# NFT-v1_0.net
KiCad netlist of a schematic drawn in EAGLE
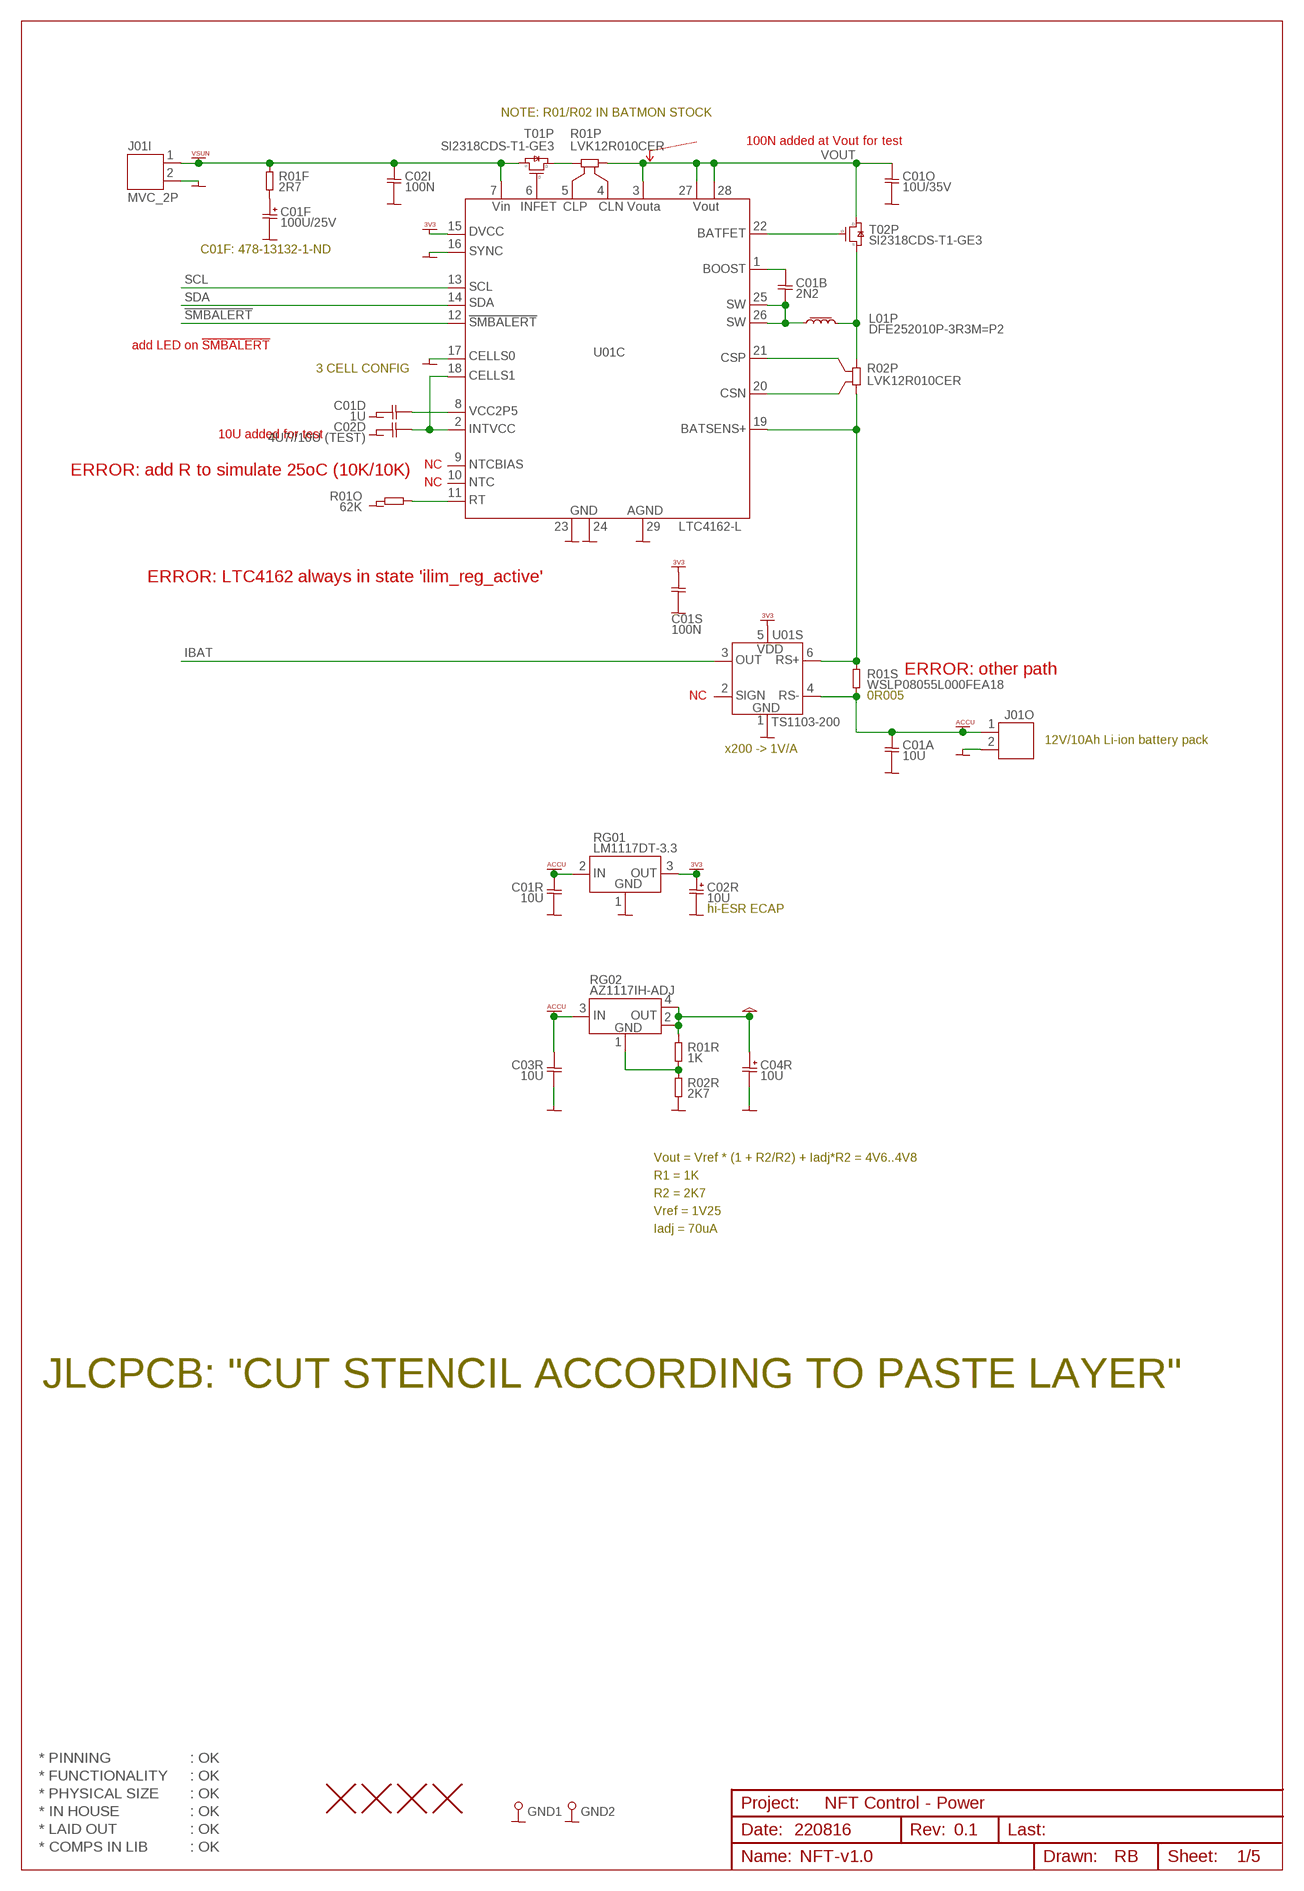
[diagram p0: schematic, sheet 1]
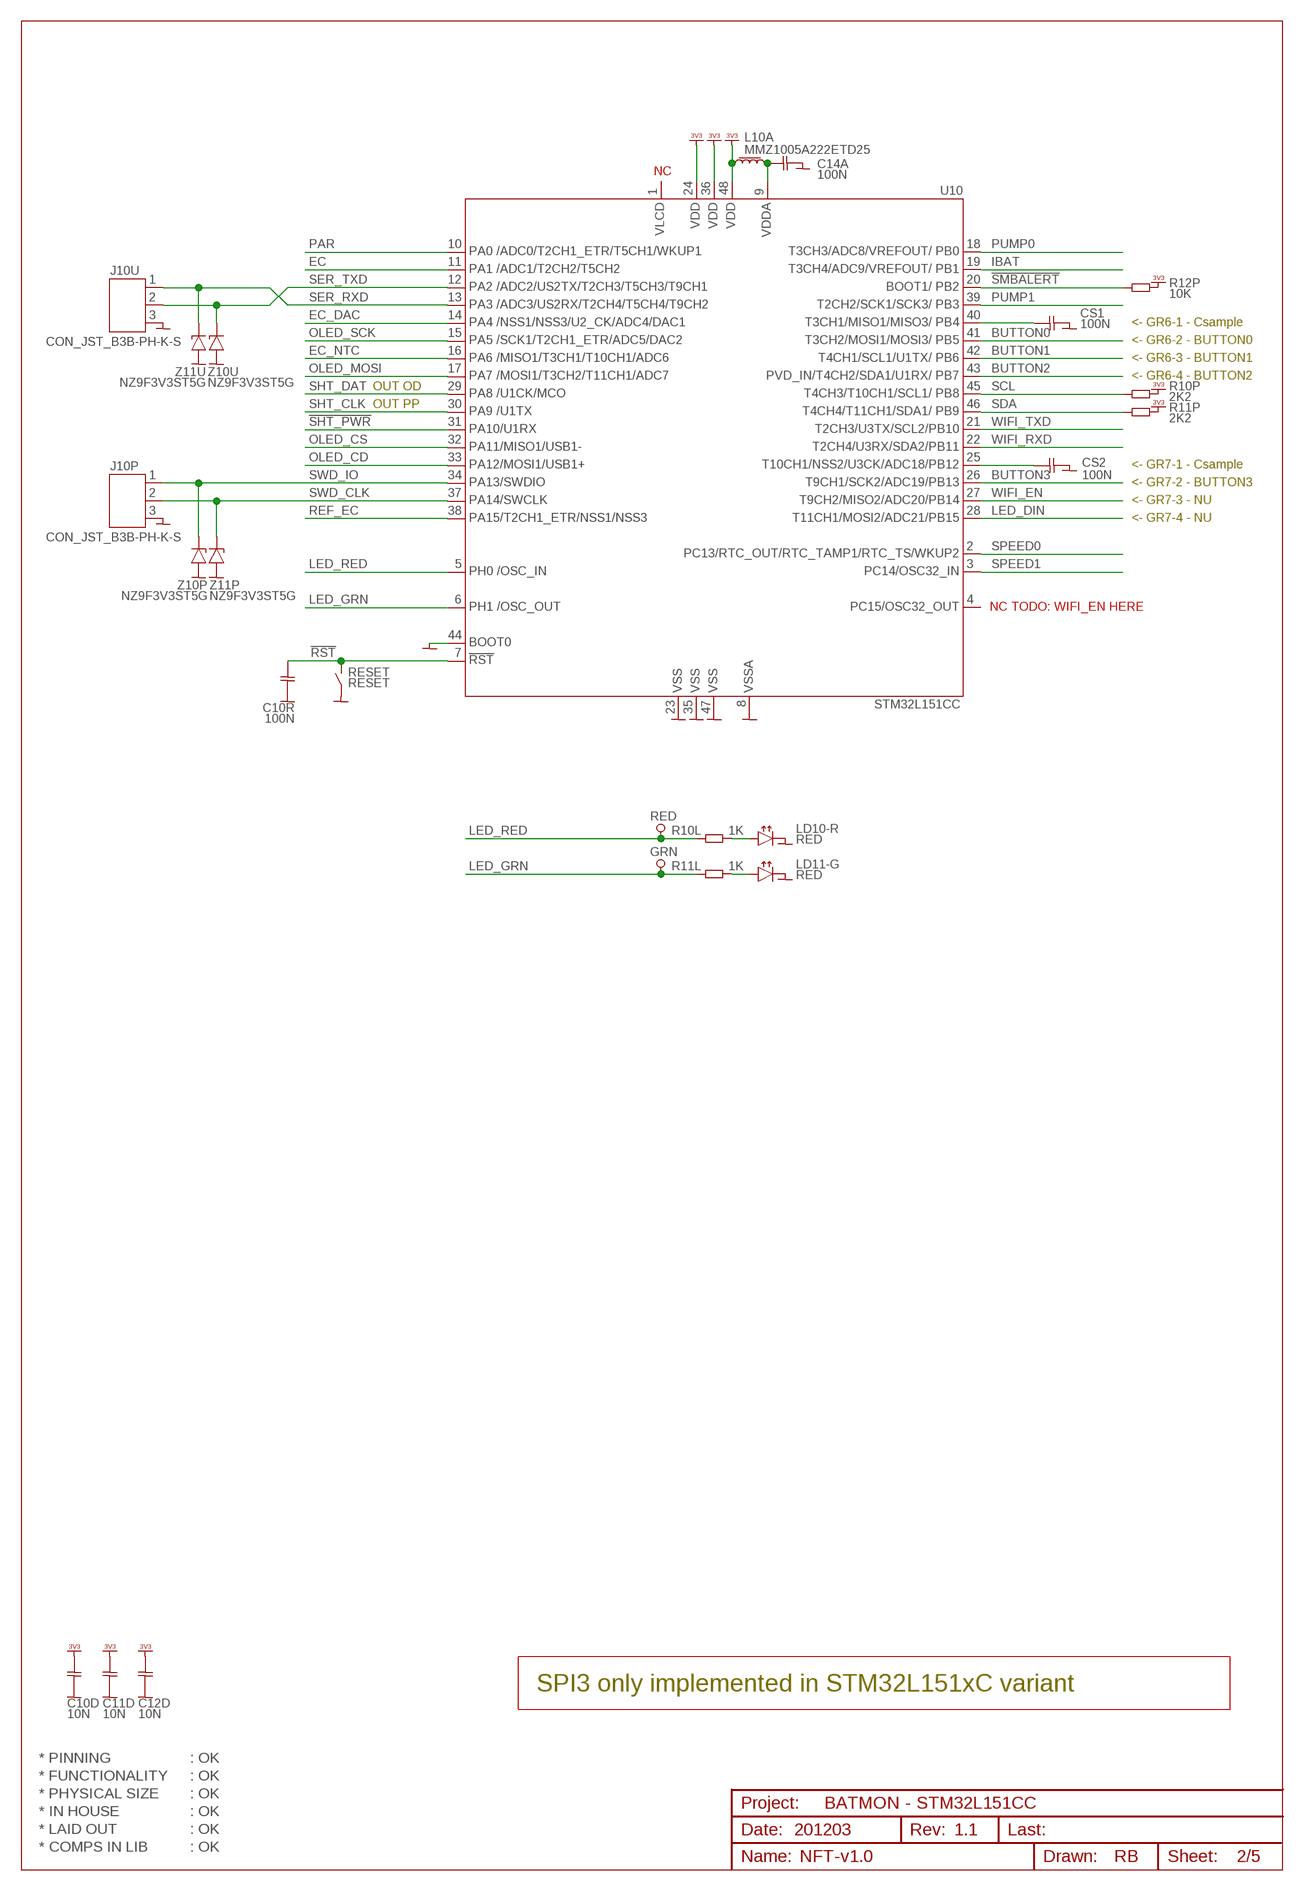
[diagram p1: schematic, sheet 2]
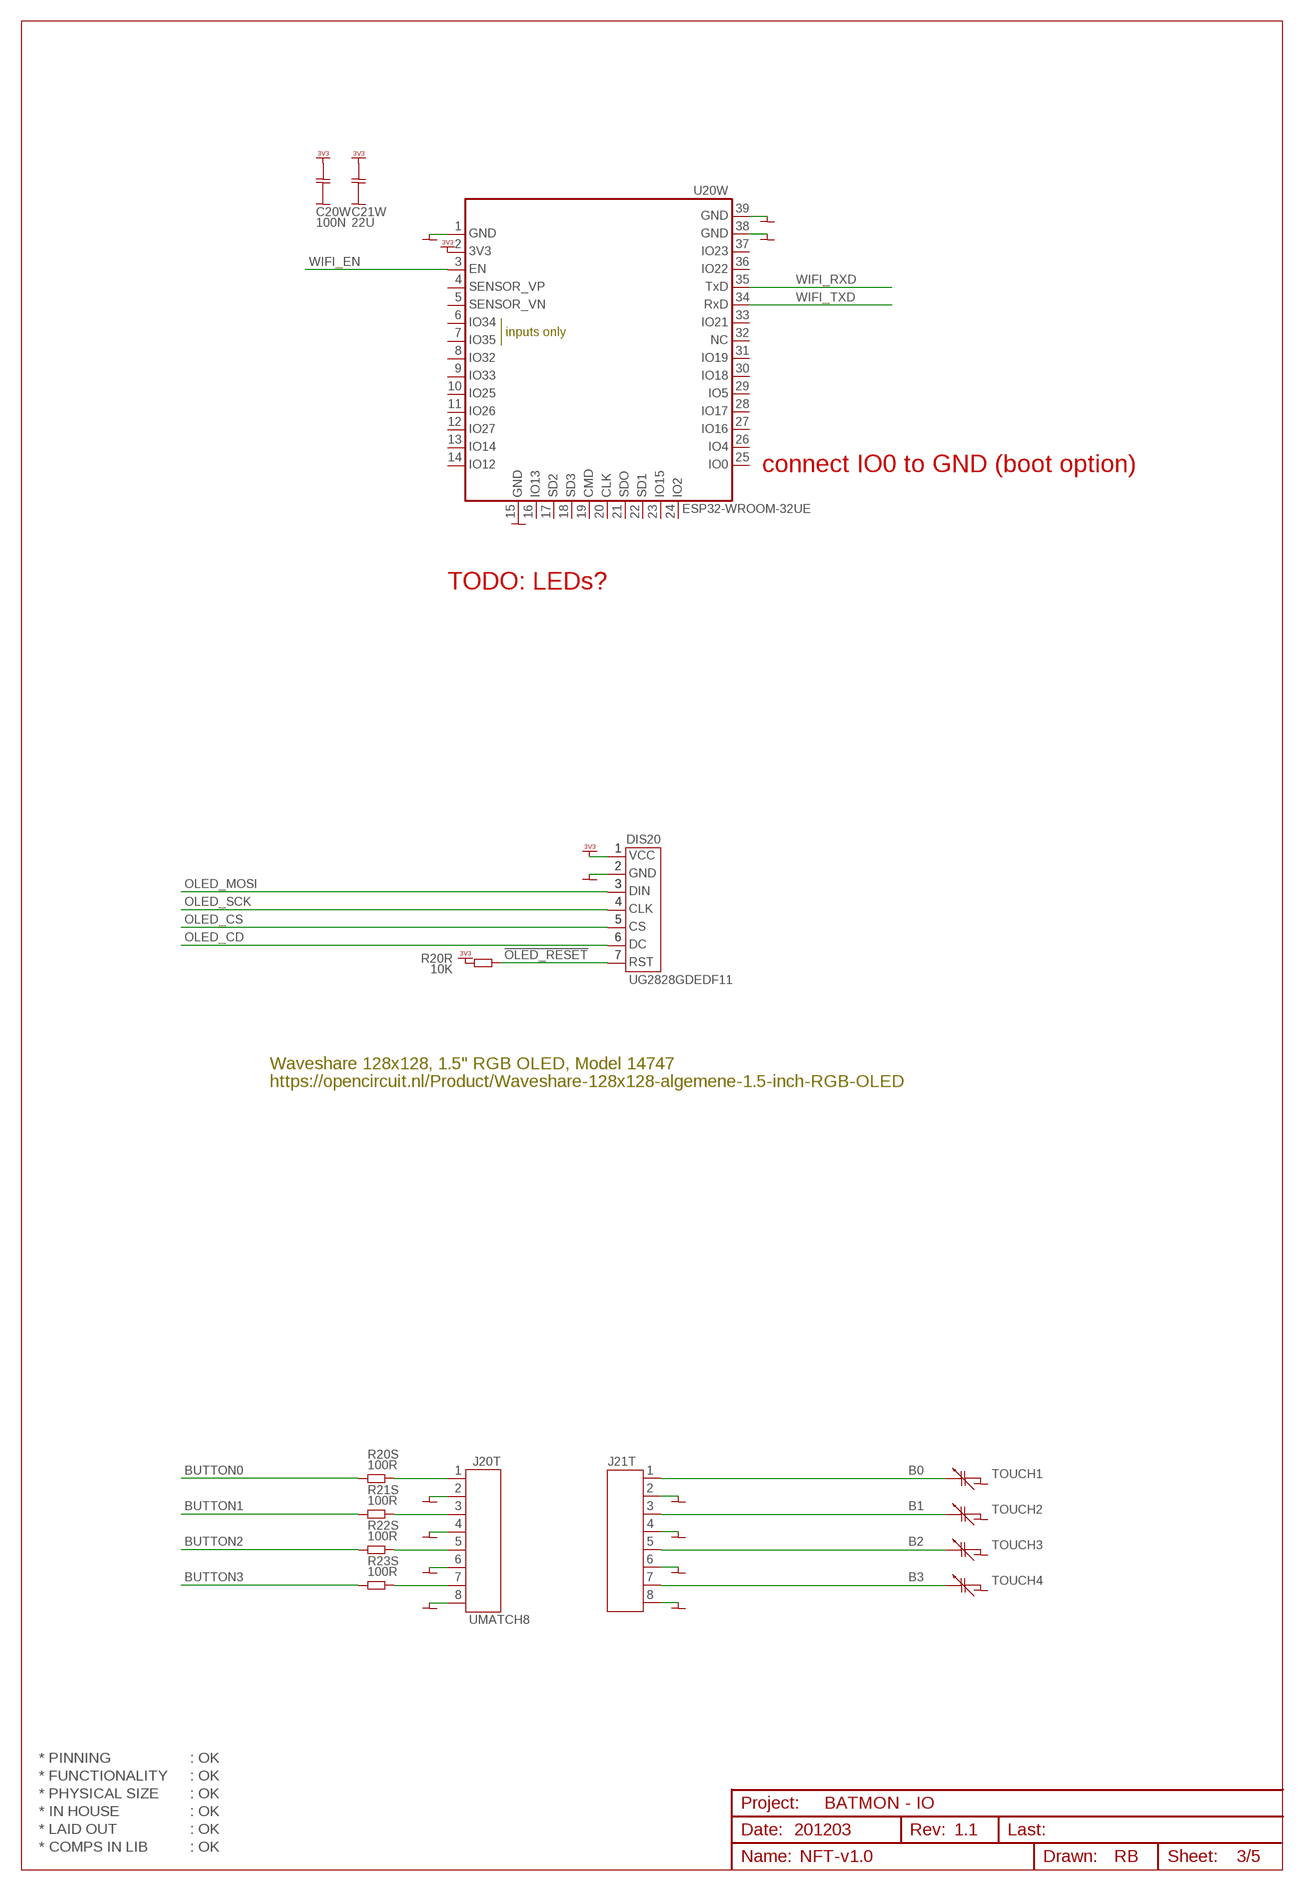
[diagram p2: schematic, sheet 3]
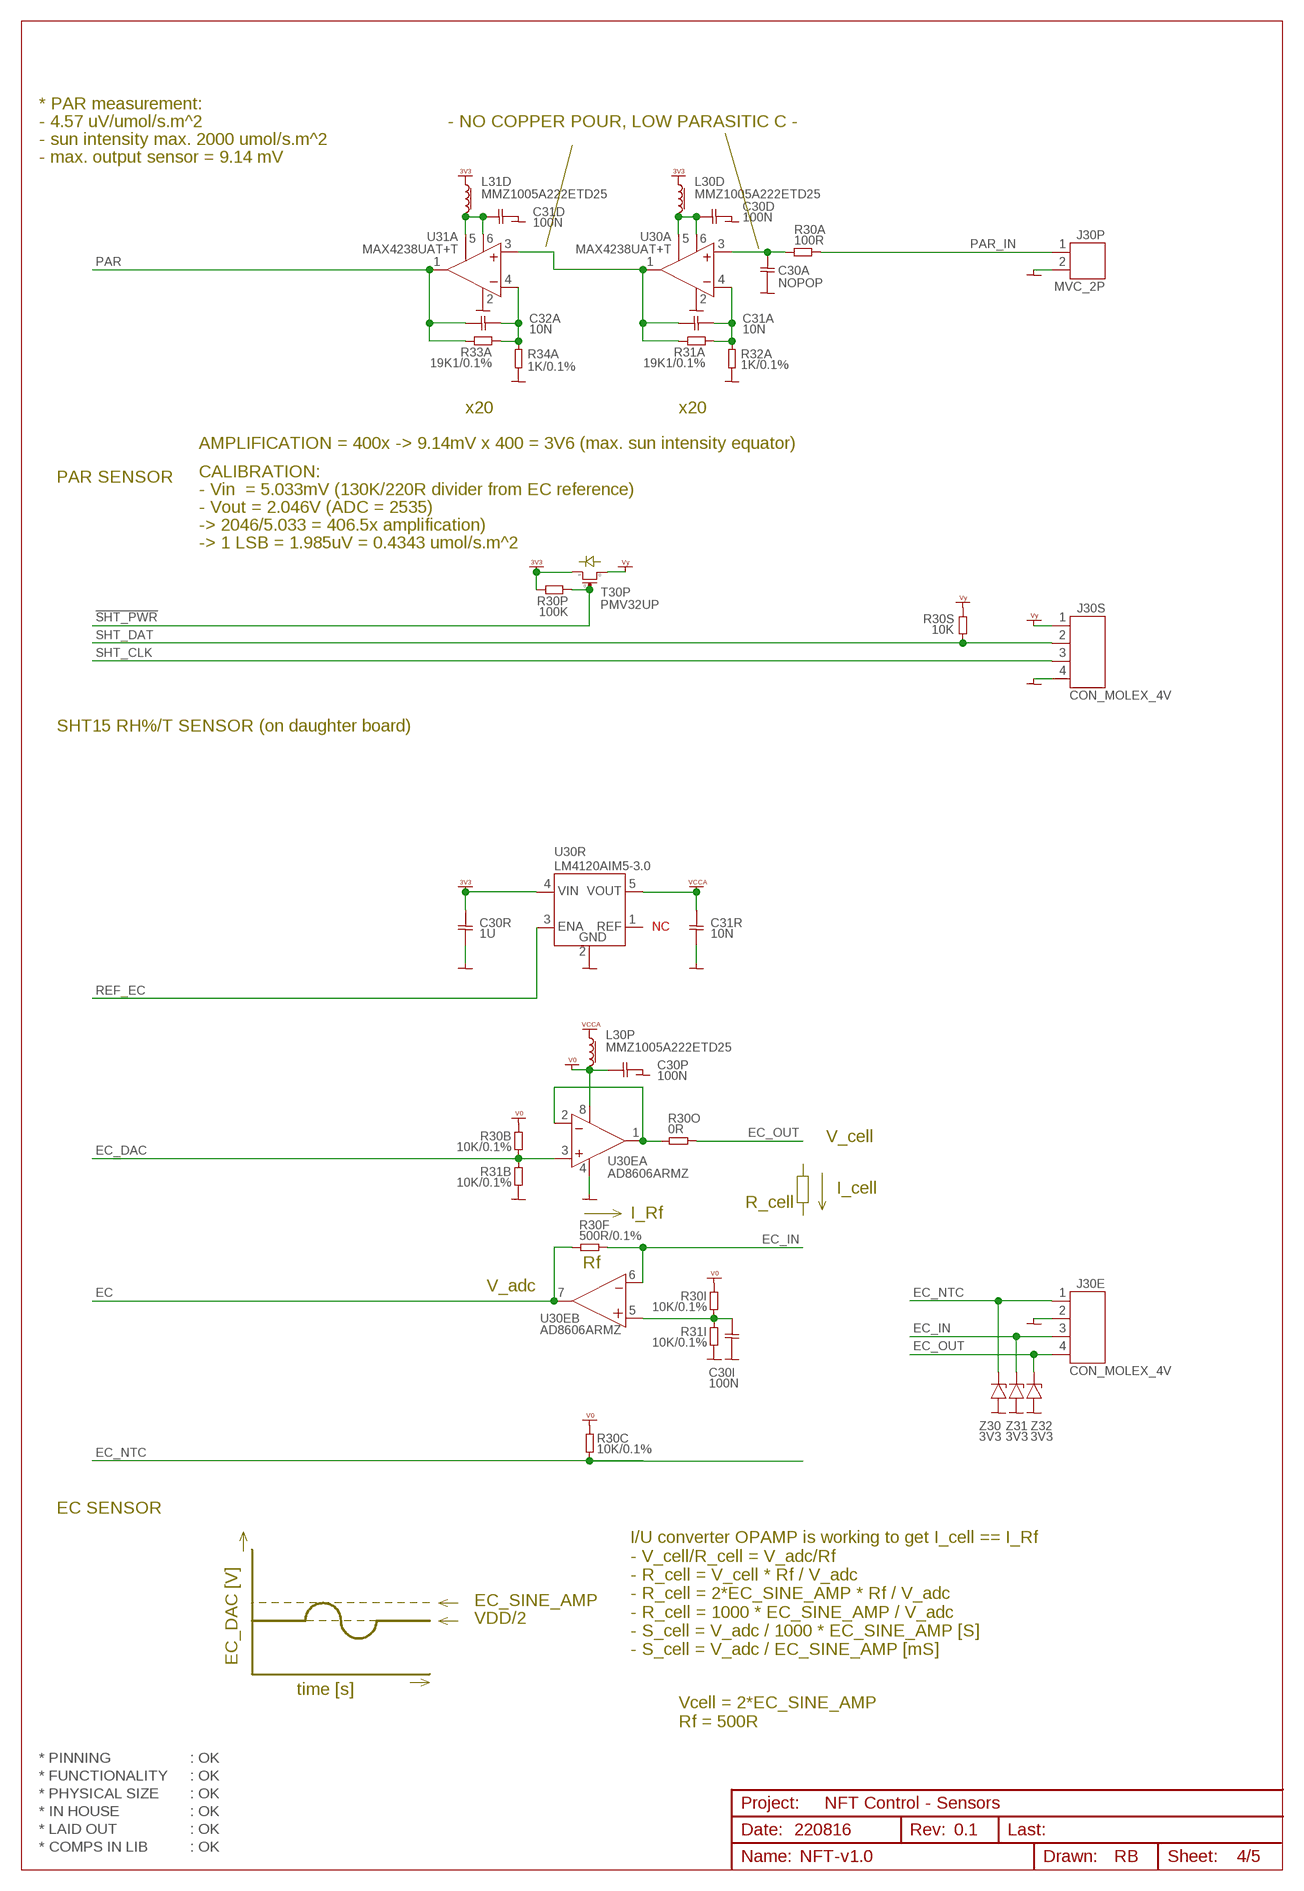
[diagram p3: schematic, sheet 4]
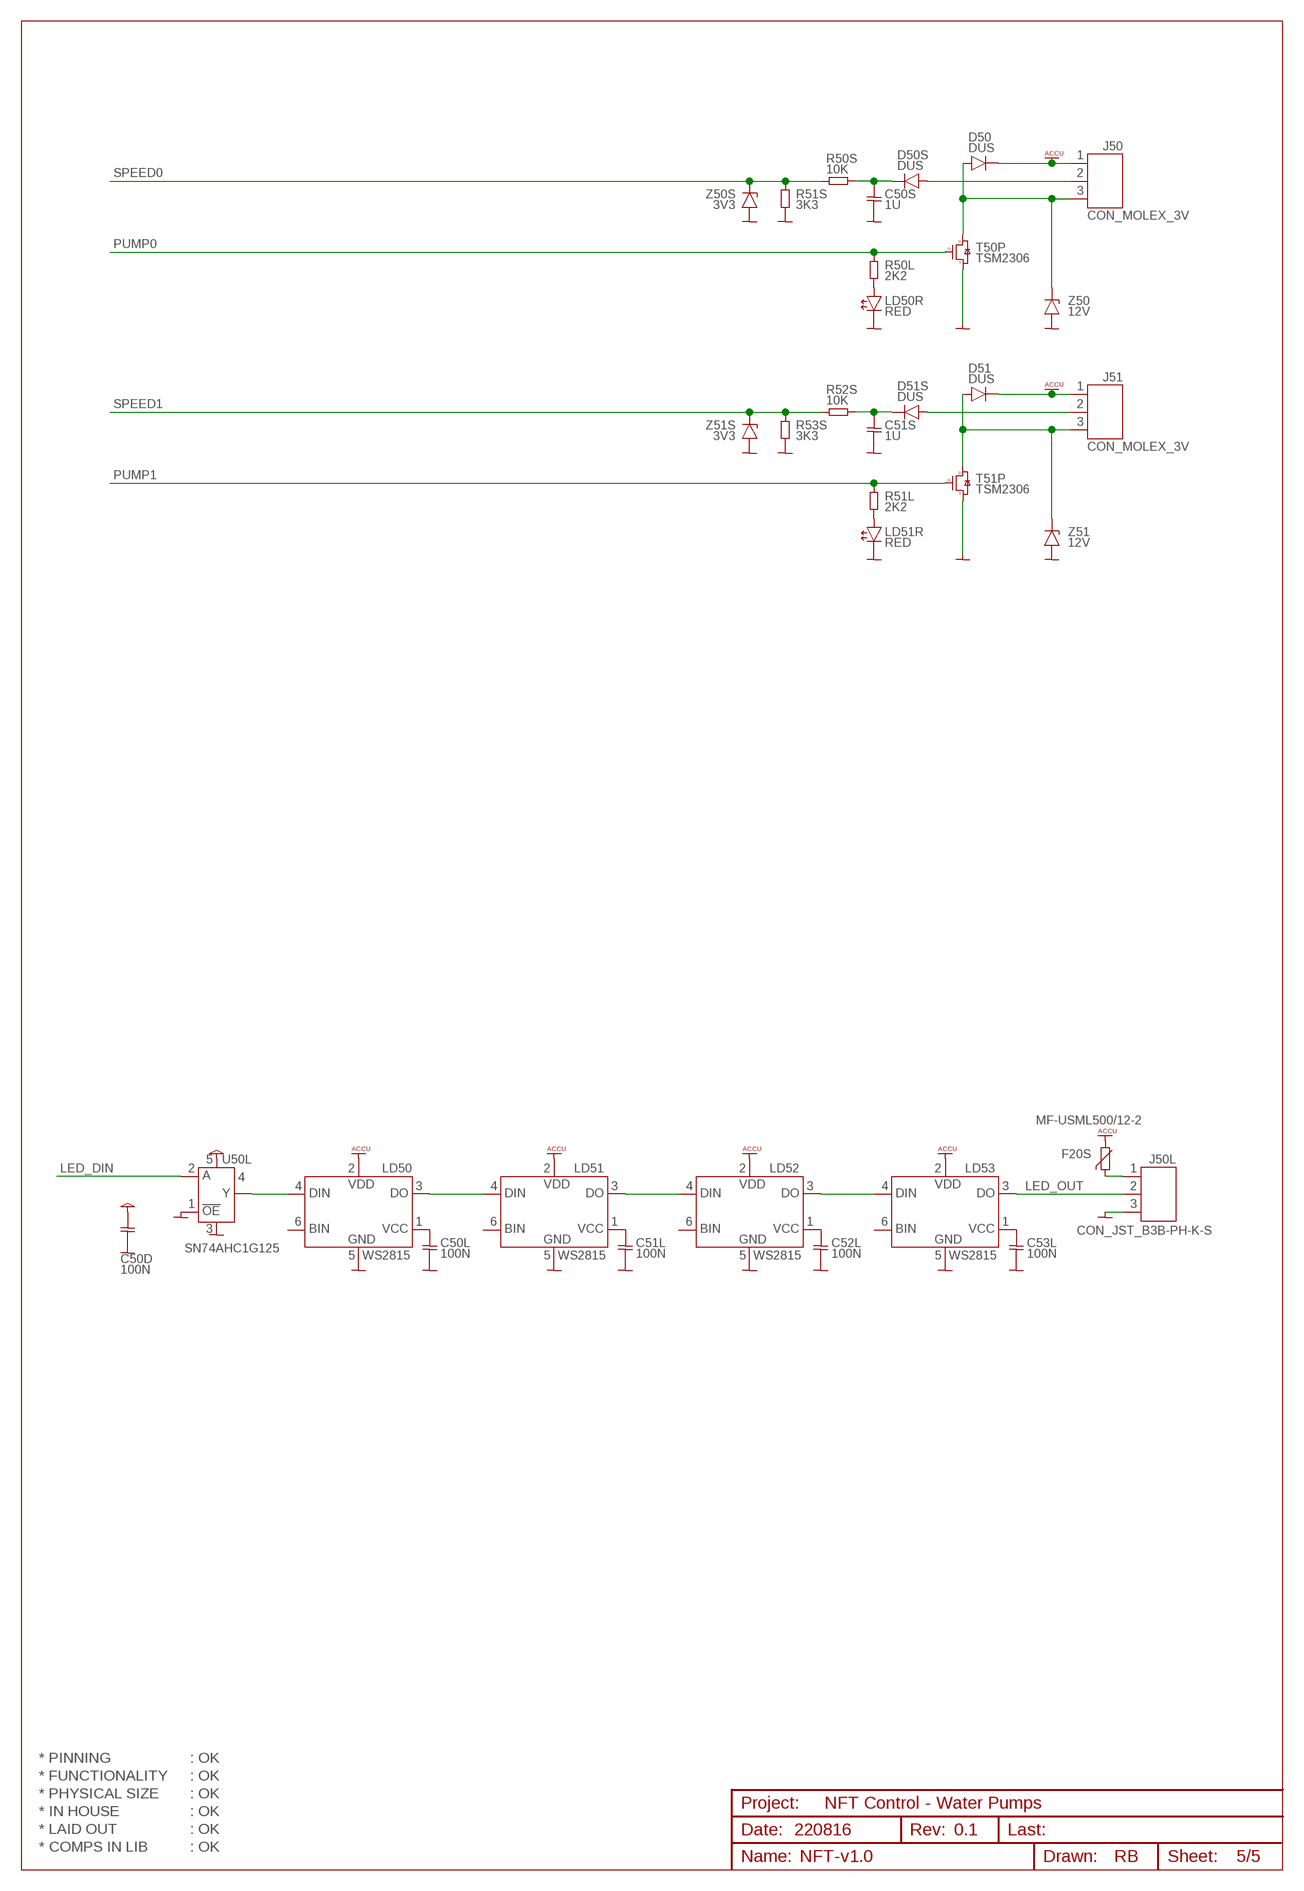
[diagram p4: schematic, sheet 5]

(export (version "E")
  (design (tool "Eeschema 10.0.6"))
  (components
    (comp (ref "C50D")
      (value "100N")
      (footprint "eagle-import:CAP0402")
      (libsource (lib "eagle-import") (part "CAP0402"))
    )
    (comp (ref "C50L")
      (value "100N")
      (footprint "eagle-import:CAP0402")
      (libsource (lib "eagle-import") (part "CAP0402"))
    )
    (comp (ref "C50S")
      (value "1U")
      (footprint "eagle-import:CAP0402")
      (libsource (lib "eagle-import") (part "CAP0402"))
    )
    (comp (ref "C51L")
      (value "100N")
      (footprint "eagle-import:CAP0402")
      (libsource (lib "eagle-import") (part "CAP0402"))
    )
    (comp (ref "C51S")
      (value "1U")
      (footprint "eagle-import:CAP0402")
      (libsource (lib "eagle-import") (part "CAP0402"))
    )
    (comp (ref "C52L")
      (value "100N")
      (footprint "eagle-import:CAP0402")
      (libsource (lib "eagle-import") (part "CAP0402"))
    )
    (comp (ref "C53L")
      (value "100N")
      (footprint "eagle-import:CAP0402")
      (libsource (lib "eagle-import") (part "CAP0402"))
    )
    (comp (ref "D50")
      (value "DUS")
      (footprint "eagle-import:DIODE_SOD323")
      (libsource (lib "eagle-import") (part "DIODE_1N4148WS"))
    )
    (comp (ref "D50S")
      (value "DUS")
      (footprint "eagle-import:DIODE_SOD323")
      (libsource (lib "eagle-import") (part "DIODE_1N4148WS"))
    )
    (comp (ref "D51")
      (value "DUS")
      (footprint "eagle-import:DIODE_SOD323")
      (libsource (lib "eagle-import") (part "DIODE_1N4148WS"))
    )
    (comp (ref "D51S")
      (value "DUS")
      (footprint "eagle-import:DIODE_SOD323")
      (libsource (lib "eagle-import") (part "DIODE_1N4148WS"))
    )
    (comp (ref "F20S")
      (value "MF-USML500/12-2")
      (footprint "eagle-import:RES1210")
      (libsource (lib "eagle-import") (part "PTC1210"))
    )
    (comp (ref "J50")
      (value "CON_MOLEX_3V")
      (footprint "eagle-import:CON_MOLEX_3V")
      (libsource (lib "eagle-import") (part "CON_MOLEX_3V"))
    )
    (comp (ref "J50L")
      (value "CON_JST_B3B-PH-K-S")
      (footprint "eagle-import:CON_JST_B3B-PH-K-S")
      (libsource (lib "eagle-import") (part "CON_JST_B3B-PH-K-S"))
    )
    (comp (ref "J51")
      (value "CON_MOLEX_3V")
      (footprint "eagle-import:CON_MOLEX_3V")
      (libsource (lib "eagle-import") (part "CON_MOLEX_3V"))
    )
    (comp (ref "LD50")
      (value "WS2815")
      (footprint "eagle-import:WS2815")
      (libsource (lib "eagle-import") (part "WS2815"))
    )
    (comp (ref "LD50R")
      (value "RED")
      (footprint "eagle-import:LED_SMD_0402")
      (libsource (lib "eagle-import") (part "LED_SMD_0402"))
    )
    (comp (ref "LD51")
      (value "WS2815")
      (footprint "eagle-import:WS2815")
      (libsource (lib "eagle-import") (part "WS2815"))
    )
    (comp (ref "LD51R")
      (value "RED")
      (footprint "eagle-import:LED_SMD_0402")
      (libsource (lib "eagle-import") (part "LED_SMD_0402"))
    )
    (comp (ref "LD52")
      (value "WS2815")
      (footprint "eagle-import:WS2815")
      (libsource (lib "eagle-import") (part "WS2815"))
    )
    (comp (ref "LD53")
      (value "WS2815")
      (footprint "eagle-import:WS2815")
      (libsource (lib "eagle-import") (part "WS2815"))
    )
    (comp (ref "R50L")
      (value "2K2")
      (footprint "eagle-import:RES0402")
      (libsource (lib "eagle-import") (part "RES0402"))
    )
    (comp (ref "R50S")
      (value "10K")
      (footprint "eagle-import:RES0402")
      (libsource (lib "eagle-import") (part "RES0402"))
    )
    (comp (ref "R51L")
      (value "2K2")
      (footprint "eagle-import:RES0402")
      (libsource (lib "eagle-import") (part "RES0402"))
    )
    (comp (ref "R51S")
      (value "3K3")
      (footprint "eagle-import:RES0402")
      (libsource (lib "eagle-import") (part "RES0402"))
    )
    (comp (ref "R52S")
      (value "10K")
      (footprint "eagle-import:RES0402")
      (libsource (lib "eagle-import") (part "RES0402"))
    )
    (comp (ref "R53S")
      (value "3K3")
      (footprint "eagle-import:RES0402")
      (libsource (lib "eagle-import") (part "RES0402"))
    )
    (comp (ref "T50P")
      (value "TSM2306")
      (footprint "eagle-import:NFET_SOT23")
      (libsource (lib "eagle-import") (part "NFET_SOT23"))
    )
    (comp (ref "T51P")
      (value "TSM2306")
      (footprint "eagle-import:NFET_SOT23")
      (libsource (lib "eagle-import") (part "NFET_SOT23"))
    )
    (comp (ref "U50L")
      (value "SN74AHC1G125")
      (footprint "eagle-import:SOT553-5")
      (libsource (lib "eagle-import") (part "SN74AHC1G125DRLR"))
    )
    (comp (ref "Z50")
      (value "12V")
      (footprint "eagle-import:ZENER_SOD80")
      (libsource (lib "eagle-import") (part "ZENER_SOD80"))
    )
    (comp (ref "Z50S")
      (value "3V3")
      (footprint "eagle-import:ZENER_SOD80")
      (libsource (lib "eagle-import") (part "ZENER_SOD80"))
    )
    (comp (ref "Z51")
      (value "12V")
      (footprint "eagle-import:ZENER_SOD80")
      (libsource (lib "eagle-import") (part "ZENER_SOD80"))
    )
    (comp (ref "Z51S")
      (value "3V3")
      (footprint "eagle-import:ZENER_SOD80")
      (libsource (lib "eagle-import") (part "ZENER_SOD80"))
    )
    (comp (ref "C10D")
      (value "10N")
      (footprint "eagle-import:CAP0402")
      (libsource (lib "eagle-import") (part "CAP0402"))
    )
    (comp (ref "C10R")
      (value "100N")
      (footprint "eagle-import:CAP0402")
      (libsource (lib "eagle-import") (part "CAP0402"))
    )
    (comp (ref "C11D")
      (value "10N")
      (footprint "eagle-import:CAP0402")
      (libsource (lib "eagle-import") (part "CAP0402"))
    )
    (comp (ref "C12D")
      (value "10N")
      (footprint "eagle-import:CAP0402")
      (libsource (lib "eagle-import") (part "CAP0402"))
    )
    (comp (ref "C14A")
      (value "100N")
      (footprint "eagle-import:CAP0402")
      (libsource (lib "eagle-import") (part "CAP0402"))
    )
    (comp (ref "CS1")
      (value "100N")
      (footprint "eagle-import:CAP0402")
      (libsource (lib "eagle-import") (part "CAP0402"))
    )
    (comp (ref "CS2")
      (value "100N")
      (footprint "eagle-import:CAP0402")
      (libsource (lib "eagle-import") (part "CAP0402"))
    )
    (comp (ref "GRN")
      (value "PIN_TEST_0.6MM")
      (footprint "eagle-import:HOLE_PTH_0.6MM")
      (libsource (lib "eagle-import") (part "PIN_TEST_0.6MM"))
    )
    (comp (ref "J10P")
      (value "CON_JST_B3B-PH-K-S")
      (footprint "eagle-import:CON_JST_B3B-PH-K-S")
      (libsource (lib "eagle-import") (part "CON_JST_B3B-PH-K-S"))
    )
    (comp (ref "J10U")
      (value "CON_JST_B3B-PH-K-S")
      (footprint "eagle-import:CON_JST_B3B-PH-K-S")
      (libsource (lib "eagle-import") (part "CON_JST_B3B-PH-K-S"))
    )
    (comp (ref "L10A")
      (value "MMZ1005A222ETD25")
      (footprint "eagle-import:L_0402")
      (libsource (lib "eagle-import") (part "L_0402_LOSSY"))
    )
    (comp (ref "LD10-R")
      (value "RED")
      (footprint "eagle-import:LED_SMD_0402")
      (libsource (lib "eagle-import") (part "LED_SMD_0402"))
    )
    (comp (ref "LD11-G")
      (value "RED")
      (footprint "eagle-import:LED_SMD_0402")
      (libsource (lib "eagle-import") (part "LED_SMD_0402"))
    )
    (comp (ref "R10L")
      (value "1K")
      (footprint "eagle-import:RES0402")
      (libsource (lib "eagle-import") (part "RES0402"))
    )
    (comp (ref "R10P")
      (value "2K2")
      (footprint "eagle-import:RES0402")
      (libsource (lib "eagle-import") (part "RES0402"))
    )
    (comp (ref "R11L")
      (value "1K")
      (footprint "eagle-import:RES0402")
      (libsource (lib "eagle-import") (part "RES0402"))
    )
    (comp (ref "R11P")
      (value "2K2")
      (footprint "eagle-import:RES0402")
      (libsource (lib "eagle-import") (part "RES0402"))
    )
    (comp (ref "R12P")
      (value "10K")
      (footprint "eagle-import:RES0402")
      (libsource (lib "eagle-import") (part "RES0402"))
    )
    (comp (ref "RED")
      (value "PIN_TEST_0.6MM")
      (footprint "eagle-import:HOLE_PTH_0.6MM")
      (libsource (lib "eagle-import") (part "PIN_TEST_0.6MM"))
    )
    (comp (ref "RESET")
      (value "RESET")
      (footprint "eagle-import:SWITCH_SMD_PBUTTON_2P")
      (libsource (lib "eagle-import") (part "SWITCH_PUSHBUTTON"))
    )
    (comp (ref "U10")
      (value "STM32L151CC")
      (footprint "eagle-import:LQFP48")
      (libsource (lib "eagle-import") (part "STM32L151CC"))
    )
    (comp (ref "Z10P")
      (value "NZ9F3V3ST5G")
      (footprint "eagle-import:ZENER_SOD923")
      (libsource (lib "eagle-import") (part "ZENER_SOD923"))
    )
    (comp (ref "Z10U")
      (value "NZ9F3V3ST5G")
      (footprint "eagle-import:ZENER_SOD923")
      (libsource (lib "eagle-import") (part "ZENER_SOD923"))
    )
    (comp (ref "Z11P")
      (value "NZ9F3V3ST5G")
      (footprint "eagle-import:ZENER_SOD923")
      (libsource (lib "eagle-import") (part "ZENER_SOD923"))
    )
    (comp (ref "Z11U")
      (value "NZ9F3V3ST5G")
      (footprint "eagle-import:ZENER_SOD923")
      (libsource (lib "eagle-import") (part "ZENER_SOD923"))
    )
    (comp (ref "C20W")
      (value "100N")
      (footprint "eagle-import:CAP0402")
      (libsource (lib "eagle-import") (part "CAP0402"))
    )
    (comp (ref "C21W")
      (value "22U")
      (footprint "eagle-import:CAP0805")
      (libsource (lib "eagle-import") (part "CAP0805"))
    )
    (comp (ref "DIS20")
      (value "UG2828GDEDF11")
      (footprint "eagle-import:WAVESHARE_1.5_OLED128X128")
      (libsource (lib "eagle-import") (part "WAVESHARE_1.5{dblquote}OLED128X128"))
    )
    (comp (ref "J20T")
      (value "UMATCH8")
      (footprint "eagle-import:CON_MICROMATCH_TOP_8F")
      (libsource (lib "eagle-import") (part "CON_MICROMATCH_8F-TOP"))
    )
    (comp (ref "J21T")
      (value "CON_MICROMATCH_8F_SMD-TOP")
      (footprint "eagle-import:CON_MICROMATCH_TOP_8F_SMD")
      (libsource (lib "eagle-import") (part "CON_MICROMATCH_8F_SMD-TOP"))
    )
    (comp (ref "R20R")
      (value "10K")
      (footprint "eagle-import:RES0402")
      (libsource (lib "eagle-import") (part "RES0402"))
    )
    (comp (ref "R20S")
      (value "100R")
      (footprint "eagle-import:RES0402")
      (libsource (lib "eagle-import") (part "RES0402"))
    )
    (comp (ref "R21S")
      (value "100R")
      (footprint "eagle-import:RES0402")
      (libsource (lib "eagle-import") (part "RES0402"))
    )
    (comp (ref "R22S")
      (value "100R")
      (footprint "eagle-import:RES0402")
      (libsource (lib "eagle-import") (part "RES0402"))
    )
    (comp (ref "R23S")
      (value "100R")
      (footprint "eagle-import:RES0402")
      (libsource (lib "eagle-import") (part "RES0402"))
    )
    (comp (ref "TOUCH1")
      (value "CAP_TOUCH_ROUND_10MM_SINGLE")
      (footprint "eagle-import:CAP_TOUCH_ROUND_10MM_SINGLE")
      (libsource (lib "eagle-import") (part "CAP_TOUCH_ROUND_10MM_SINGLE"))
    )
    (comp (ref "TOUCH2")
      (value "CAP_TOUCH_ROUND_10MM_SINGLE")
      (footprint "eagle-import:CAP_TOUCH_ROUND_10MM_SINGLE")
      (libsource (lib "eagle-import") (part "CAP_TOUCH_ROUND_10MM_SINGLE"))
    )
    (comp (ref "TOUCH3")
      (value "CAP_TOUCH_ROUND_10MM_SINGLE")
      (footprint "eagle-import:CAP_TOUCH_ROUND_10MM_SINGLE")
      (libsource (lib "eagle-import") (part "CAP_TOUCH_ROUND_10MM_SINGLE"))
    )
    (comp (ref "TOUCH4")
      (value "CAP_TOUCH_ROUND_10MM_SINGLE")
      (footprint "eagle-import:CAP_TOUCH_ROUND_10MM_SINGLE")
      (libsource (lib "eagle-import") (part "CAP_TOUCH_ROUND_10MM_SINGLE"))
    )
    (comp (ref "U20W")
      (value "ESP32-WROOM-32UE")
      (footprint "eagle-import:ESP32-WROOM-32UE")
      (libsource (lib "eagle-import") (part "ESP32-WROOM-32UE"))
    )
    (comp (ref "C01A")
      (value "10U")
      (footprint "eagle-import:CAP0805")
      (libsource (lib "eagle-import") (part "CAP0805"))
    )
    (comp (ref "C01B")
      (value "2N2")
      (footprint "eagle-import:CAP0402")
      (libsource (lib "eagle-import") (part "CAP0402"))
    )
    (comp (ref "C01D")
      (value "1U")
      (footprint "eagle-import:CAP0402")
      (libsource (lib "eagle-import") (part "CAP0402"))
    )
    (comp (ref "C01F")
      (value "100U/25V")
      (footprint "eagle-import:ECAP_SMD")
      (libsource (lib "eagle-import") (part "ECAP_SMD"))
    )
    (comp (ref "C01O")
      (value "10U/35V")
      (footprint "eagle-import:CAP0805")
      (libsource (lib "eagle-import") (part "CAP0805"))
    )
    (comp (ref "C01R")
      (value "10U")
      (footprint "eagle-import:CAP0603")
      (libsource (lib "eagle-import") (part "CAP0603"))
    )
    (comp (ref "C01S")
      (value "100N")
      (footprint "eagle-import:CAP0402")
      (libsource (lib "eagle-import") (part "CAP0402"))
    )
    (comp (ref "C02D")
      (value "4U7//10U (TEST)")
      (footprint "eagle-import:CAP0402")
      (libsource (lib "eagle-import") (part "CAP0402"))
    )
    (comp (ref "C02I")
      (value "100N")
      (footprint "eagle-import:CAP0402")
      (libsource (lib "eagle-import") (part "CAP0402"))
    )
    (comp (ref "C02R")
      (value "10U")
      (footprint "eagle-import:ECAP_SMA")
      (libsource (lib "eagle-import") (part "ECAP_SMA"))
    )
    (comp (ref "C03R")
      (value "10U")
      (footprint "eagle-import:CAP0603")
      (libsource (lib "eagle-import") (part "CAP0603"))
    )
    (comp (ref "C04R")
      (value "10U")
      (footprint "eagle-import:ECAP_SMA")
      (libsource (lib "eagle-import") (part "ECAP_SMA"))
    )
    (comp (ref "GND1")
      (value "PIN_TEST")
      (footprint "eagle-import:HOLE_PTH_0.8MM")
      (libsource (lib "eagle-import") (part "PIN_TEST"))
    )
    (comp (ref "GND2")
      (value "PIN_TEST")
      (footprint "eagle-import:HOLE_PTH_0.8MM")
      (libsource (lib "eagle-import") (part "PIN_TEST"))
    )
    (comp (ref "H1")
      (value "HOLE_NPTH_3.2MM")
      (footprint "eagle-import:HOLE_NPTH_3.2MM")
      (libsource (lib "eagle-import") (part "HOLE_NPTH_3.2MM"))
    )
    (comp (ref "H2")
      (value "HOLE_NPTH_3.2MM")
      (footprint "eagle-import:HOLE_NPTH_3.2MM")
      (libsource (lib "eagle-import") (part "HOLE_NPTH_3.2MM"))
    )
    (comp (ref "H3")
      (value "HOLE_NPTH_3.2MM")
      (footprint "eagle-import:HOLE_NPTH_3.2MM")
      (libsource (lib "eagle-import") (part "HOLE_NPTH_3.2MM"))
    )
    (comp (ref "H4")
      (value "HOLE_NPTH_3.2MM")
      (footprint "eagle-import:HOLE_NPTH_3.2MM")
      (libsource (lib "eagle-import") (part "HOLE_NPTH_3.2MM"))
    )
    (comp (ref "J01I")
      (value "MVC_2P")
      (footprint "eagle-import:CON_PHOENIX_COMBICON_MCV_HEADER_P")
      (libsource (lib "eagle-import") (part "CON_PHOENIX_COMBICON_MCV_HEADER_2P"))
    )
    (comp (ref "J01O")
      (value "CON_PHOENIX_COMBICON_MCV_HEADER_2P")
      (footprint "eagle-import:CON_PHOENIX_COMBICON_MCV_HEADER_P")
      (libsource (lib "eagle-import") (part "CON_PHOENIX_COMBICON_MCV_HEADER_2P"))
    )
    (comp (ref "L01P")
      (value "DFE252010P-3R3M=P2")
      (footprint "eagle-import:L_1008")
      (libsource (lib "eagle-import") (part "L_1008"))
    )
    (comp (ref "R01F")
      (value "2R7")
      (footprint "eagle-import:RES0603")
      (libsource (lib "eagle-import") (part "RES0603"))
    )
    (comp (ref "R01O")
      (value "62K")
      (footprint "eagle-import:RES0402")
      (libsource (lib "eagle-import") (part "RES0402"))
    )
    (comp (ref "R01P")
      (value "LVK12R010CER")
      (footprint "eagle-import:RES1206_LVK12R010CER")
      (libsource (lib "eagle-import") (part "RES1206_LVK12R010CER1206"))
    )
    (comp (ref "R01R")
      (value "1K")
      (footprint "eagle-import:RES0402")
      (libsource (lib "eagle-import") (part "RES0402"))
    )
    (comp (ref "R01S")
      (value "WSLP08055L000FEA18")
      (footprint "eagle-import:RES0805")
      (libsource (lib "eagle-import") (part "RES0805"))
    )
    (comp (ref "R02P")
      (value "LVK12R010CER")
      (footprint "eagle-import:RES1206_LVK12R010CER")
      (libsource (lib "eagle-import") (part "RES1206_LVK12R010CER1206"))
    )
    (comp (ref "R02R")
      (value "2K7")
      (footprint "eagle-import:RES0402")
      (libsource (lib "eagle-import") (part "RES0402"))
    )
    (comp (ref "RG01")
      (value "LM1117DT-3.3")
      (footprint "eagle-import:TO252")
      (libsource (lib "eagle-import") (part "LM1117DT-3.3"))
    )
    (comp (ref "RG02")
      (value "AZ1117IH-ADJ")
      (footprint "eagle-import:SOT223")
      (libsource (lib "eagle-import") (part "AZ1117IH-ADJ"))
    )
    (comp (ref "T01P")
      (value "SI2318CDS-T1-GE3")
      (footprint "eagle-import:NFET_SOT23")
      (libsource (lib "eagle-import") (part "NFET_SOT23"))
    )
    (comp (ref "T02P")
      (value "SI2318CDS-T1-GE3")
      (footprint "eagle-import:NFET_SOT23")
      (libsource (lib "eagle-import") (part "NFET_SOT23"))
    )
    (comp (ref "U01C")
      (value "LTC4162-L")
      (footprint "eagle-import:QFN28_4X5")
      (libsource (lib "eagle-import") (part "LTC4162-L"))
    )
    (comp (ref "U01S")
      (value "TS1103-200")
      (footprint "eagle-import:SOT23-6")
      (libsource (lib "eagle-import") (part "TS1103-200"))
    )
    (comp (ref "C30A")
      (value "NOPOP")
      (footprint "eagle-import:CAP0402")
      (libsource (lib "eagle-import") (part "CAP0402"))
    )
    (comp (ref "C30D")
      (value "100N")
      (footprint "eagle-import:CAP0402")
      (libsource (lib "eagle-import") (part "CAP0402"))
    )
    (comp (ref "C30I")
      (value "100N")
      (footprint "eagle-import:CAP0402")
      (libsource (lib "eagle-import") (part "CAP0402"))
    )
    (comp (ref "C30P")
      (value "100N")
      (footprint "eagle-import:CAP0402")
      (libsource (lib "eagle-import") (part "CAP0402"))
    )
    (comp (ref "C30R")
      (value "1U")
      (footprint "eagle-import:CAP0402")
      (libsource (lib "eagle-import") (part "CAP0402"))
    )
    (comp (ref "C31A")
      (value "10N")
      (footprint "eagle-import:CAP0402")
      (libsource (lib "eagle-import") (part "CAP0402"))
    )
    (comp (ref "C31D")
      (value "100N")
      (footprint "eagle-import:CAP0402")
      (libsource (lib "eagle-import") (part "CAP0402"))
    )
    (comp (ref "C31R")
      (value "10N")
      (footprint "eagle-import:CAP0402")
      (libsource (lib "eagle-import") (part "CAP0402"))
    )
    (comp (ref "C32A")
      (value "10N")
      (footprint "eagle-import:CAP0402")
      (libsource (lib "eagle-import") (part "CAP0402"))
    )
    (comp (ref "J30E")
      (value "CON_MOLEX_4V")
      (footprint "eagle-import:CON_MOLEX_4V")
      (libsource (lib "eagle-import") (part "CON_MOLEX_4V"))
    )
    (comp (ref "J30P")
      (value "MVC_2P")
      (footprint "eagle-import:CON_PHOENIX_COMBICON_MCV_HEADER_P")
      (libsource (lib "eagle-import") (part "CON_PHOENIX_COMBICON_MCV_HEADER_2P"))
    )
    (comp (ref "J30S")
      (value "CON_MOLEX_4V")
      (footprint "eagle-import:CON_MOLEX_4V")
      (libsource (lib "eagle-import") (part "CON_MOLEX_4V"))
    )
    (comp (ref "L30D")
      (value "MMZ1005A222ETD25")
      (footprint "eagle-import:L_0402")
      (libsource (lib "eagle-import") (part "L_0402_LOSSY"))
    )
    (comp (ref "L30P")
      (value "MMZ1005A222ETD25")
      (footprint "eagle-import:L_0402")
      (libsource (lib "eagle-import") (part "L_0402_LOSSY"))
    )
    (comp (ref "L31D")
      (value "MMZ1005A222ETD25")
      (footprint "eagle-import:L_0402")
      (libsource (lib "eagle-import") (part "L_0402_LOSSY"))
    )
    (comp (ref "R30A")
      (value "100R")
      (footprint "eagle-import:RES0402")
      (libsource (lib "eagle-import") (part "RES0402"))
    )
    (comp (ref "R30B")
      (value "10K/0.1%")
      (footprint "eagle-import:RES0402")
      (libsource (lib "eagle-import") (part "RES0402"))
    )
    (comp (ref "R30C")
      (value "10K/0.1%")
      (footprint "eagle-import:RES0402")
      (libsource (lib "eagle-import") (part "RES0402"))
    )
    (comp (ref "R30F")
      (value "500R/0.1%")
      (footprint "eagle-import:RES0402")
      (libsource (lib "eagle-import") (part "RES0402"))
    )
    (comp (ref "R30I")
      (value "10K/0.1%")
      (footprint "eagle-import:RES0402")
      (libsource (lib "eagle-import") (part "RES0402"))
    )
    (comp (ref "R30O")
      (value "0R")
      (footprint "eagle-import:RES0402")
      (libsource (lib "eagle-import") (part "RES0402"))
    )
    (comp (ref "R30P")
      (value "100K")
      (footprint "eagle-import:RES0402")
      (libsource (lib "eagle-import") (part "RES0402"))
    )
    (comp (ref "R30S")
      (value "10K")
      (footprint "eagle-import:RES0402")
      (libsource (lib "eagle-import") (part "RES0402"))
    )
    (comp (ref "R31A")
      (value "19K1/0.1%")
      (footprint "eagle-import:RES0402")
      (libsource (lib "eagle-import") (part "RES0402"))
    )
    (comp (ref "R31B")
      (value "10K/0.1%")
      (footprint "eagle-import:RES0402")
      (libsource (lib "eagle-import") (part "RES0402"))
    )
    (comp (ref "R31I")
      (value "10K/0.1%")
      (footprint "eagle-import:RES0402")
      (libsource (lib "eagle-import") (part "RES0402"))
    )
    (comp (ref "R32A")
      (value "1K/0.1%")
      (footprint "eagle-import:RES0402")
      (libsource (lib "eagle-import") (part "RES0402"))
    )
    (comp (ref "R33A")
      (value "19K1/0.1%")
      (footprint "eagle-import:RES0402")
      (libsource (lib "eagle-import") (part "RES0402"))
    )
    (comp (ref "R34A")
      (value "1K/0.1%")
      (footprint "eagle-import:RES0402")
      (libsource (lib "eagle-import") (part "RES0402"))
    )
    (comp (ref "T30P")
      (value "PMV32UP")
      (footprint "eagle-import:PFET_SOT23")
      (libsource (lib "eagle-import") (part "PFET_SOT23"))
    )
    (comp (ref "U30A")
      (value "MAX4238UAT+T")
      (footprint "eagle-import:SOT23-6")
      (libsource (lib "eagle-import") (part "MAX4238UAT+T"))
    )
    (comp (ref "U30E")
      (value "AD8606ARMZ")
      (footprint "eagle-import:MSOP8")
      (libsource (lib "eagle-import") (part "AD8606ARMZ"))
    )
    (comp (ref "U30R")
      (value "LM4120AIM5-3.0")
      (footprint "eagle-import:SOT23-5")
      (libsource (lib "eagle-import") (part "LM4120AIM5-3.0"))
    )
    (comp (ref "U31A")
      (value "MAX4238UAT+T")
      (footprint "eagle-import:SOT23-6")
      (libsource (lib "eagle-import") (part "MAX4238UAT+T"))
    )
    (comp (ref "Z30")
      (value "3V3")
      (footprint "eagle-import:ZENER_SOD80")
      (libsource (lib "eagle-import") (part "ZENER_SOD80"))
    )
    (comp (ref "Z31")
      (value "3V3")
      (footprint "eagle-import:ZENER_SOD80")
      (libsource (lib "eagle-import") (part "ZENER_SOD80"))
    )
    (comp (ref "Z32")
      (value "3V3")
      (footprint "eagle-import:ZENER_SOD80")
      (libsource (lib "eagle-import") (part "ZENER_SOD80"))
    )
  )
  (nets
    (net (code "1") (name "ACCU") (class "Default")
      (node (ref "C01A") (pin "1") (pinfunction "1_1") (pintype "passive"))
      (node (ref "C01R") (pin "1") (pinfunction "1_1") (pintype "passive"))
      (node (ref "C03R") (pin "1") (pinfunction "1_1") (pintype "passive"))
      (node (ref "D50") (pin "1-") (pinfunction "-_1-") (pintype "passive"))
      (node (ref "D51") (pin "1-") (pinfunction "-_1-") (pintype "passive"))
      (node (ref "F20S") (pin "2") (pinfunction "P$2_2") (pintype "passive"))
      (node (ref "J01O") (pin "1") (pinfunction "1_1") (pintype "passive"))
      (node (ref "J50") (pin "1") (pinfunction "1_1") (pintype "passive"))
      (node (ref "J51") (pin "1") (pinfunction "1_1") (pintype "passive"))
      (node (ref "LD50") (pin "2") (pinfunction "2.VDD_2") (pintype "passive"))
      (node (ref "LD51") (pin "2") (pinfunction "2.VDD_2") (pintype "passive"))
      (node (ref "LD52") (pin "2") (pinfunction "2.VDD_2") (pintype "passive"))
      (node (ref "LD53") (pin "2") (pinfunction "2.VDD_2") (pintype "passive"))
      (node (ref "R01S") (pin "2") (pinfunction "2_2") (pintype "passive"))
      (node (ref "RG01") (pin "2") (pinfunction "2.IN_2") (pintype "passive"))
      (node (ref "RG02") (pin "3") (pinfunction "3.IN_3") (pintype "passive"))
      (node (ref "U01S") (pin "4") (pinfunction "4.RS-_4") (pintype "passive"))
    )
    (net (code "2") (name "B0") (class "Default")
      (node (ref "J20T") (pin "1") (pinfunction "1_1") (pintype "passive"))
      (node (ref "J21T") (pin "1") (pinfunction "1_1") (pintype "passive"))
      (node (ref "R20S") (pin "2") (pinfunction "2_2") (pintype "passive"))
      (node (ref "TOUCH1") (pin "1") (pinfunction "1_1") (pintype "passive"))
    )
    (net (code "3") (name "B1") (class "Default")
      (node (ref "J20T") (pin "3") (pinfunction "3_3") (pintype "passive"))
      (node (ref "J21T") (pin "3") (pinfunction "3_3") (pintype "passive"))
      (node (ref "R21S") (pin "2") (pinfunction "2_2") (pintype "passive"))
      (node (ref "TOUCH2") (pin "1") (pinfunction "1_1") (pintype "passive"))
    )
    (net (code "4") (name "B2") (class "Default")
      (node (ref "J20T") (pin "5") (pinfunction "5_5") (pintype "passive"))
      (node (ref "J21T") (pin "5") (pinfunction "5_5") (pintype "passive"))
      (node (ref "R22S") (pin "2") (pinfunction "2_2") (pintype "passive"))
      (node (ref "TOUCH3") (pin "1") (pinfunction "1_1") (pintype "passive"))
    )
    (net (code "5") (name "B3") (class "Default")
      (node (ref "J20T") (pin "7") (pinfunction "7_7") (pintype "passive"))
      (node (ref "J21T") (pin "7") (pinfunction "7_7") (pintype "passive"))
      (node (ref "R23S") (pin "2") (pinfunction "2_2") (pintype "passive"))
      (node (ref "TOUCH4") (pin "1") (pinfunction "1_1") (pintype "passive"))
    )
    (net (code "6") (name "BUTTON0") (class "Default")
      (node (ref "R20S") (pin "1") (pinfunction "1_1") (pintype "passive"))
      (node (ref "U10") (pin "41") (pinfunction "41.PB5_41") (pintype "passive"))
    )
    (net (code "7") (name "BUTTON1") (class "Default")
      (node (ref "R21S") (pin "1") (pinfunction "1_1") (pintype "passive"))
      (node (ref "U10") (pin "42") (pinfunction "42.PB6_42") (pintype "passive"))
    )
    (net (code "8") (name "BUTTON2") (class "Default")
      (node (ref "R22S") (pin "1") (pinfunction "1_1") (pintype "passive"))
      (node (ref "U10") (pin "43") (pinfunction "43.PB7_43") (pintype "passive"))
    )
    (net (code "9") (name "BUTTON3") (class "Default")
      (node (ref "R23S") (pin "1") (pinfunction "1_1") (pintype "passive"))
      (node (ref "U10") (pin "26") (pinfunction "26.PB13_26") (pintype "passive"))
    )
    (net (code "10") (name "EC") (class "Default")
      (node (ref "R30F") (pin "2") (pinfunction "2_2") (pintype "passive"))
      (node (ref "U10") (pin "11") (pinfunction "11.PA1_11") (pintype "passive"))
      (node (ref "U30E") (pin "7") (pinfunction "7.OUT_7") (pintype "passive"))
    )
    (net (code "11") (name "EC_DAC") (class "Default")
      (node (ref "R30B") (pin "2") (pinfunction "2_2") (pintype "passive"))
      (node (ref "R31B") (pin "1") (pinfunction "1_1") (pintype "passive"))
      (node (ref "U10") (pin "14") (pinfunction "14.PA4_14") (pintype "passive"))
      (node (ref "U30E") (pin "3") (pinfunction "3.IN+_3") (pintype "passive"))
    )
    (net (code "12") (name "EC_IN") (class "Default")
      (node (ref "J30E") (pin "3") (pinfunction "3_3") (pintype "passive"))
      (node (ref "R30F") (pin "1") (pinfunction "1_1") (pintype "passive"))
      (node (ref "U30E") (pin "6") (pinfunction "6.IN-_6") (pintype "passive"))
      (node (ref "Z31") (pin "2") (pinfunction "C_2") (pintype "passive"))
    )
    (net (code "13") (name "EC_NTC") (class "Default")
      (node (ref "J30E") (pin "1") (pinfunction "1_1") (pintype "passive"))
      (node (ref "R30C") (pin "2") (pinfunction "2_2") (pintype "passive"))
      (node (ref "U10") (pin "16") (pinfunction "16.PA6_16") (pintype "passive"))
      (node (ref "Z30") (pin "2") (pinfunction "C_2") (pintype "passive"))
    )
    (net (code "14") (name "EC_OUT") (class "Default")
      (node (ref "J30E") (pin "4") (pinfunction "4_4") (pintype "passive"))
      (node (ref "R30O") (pin "1") (pinfunction "1_1") (pintype "passive"))
      (node (ref "Z32") (pin "2") (pinfunction "C_2") (pintype "passive"))
    )
    (net (code "15") (name "GND") (class "Default")
      (node (ref "C01A") (pin "2") (pinfunction "2_2") (pintype "passive"))
      (node (ref "C01D") (pin "1") (pinfunction "1_1") (pintype "passive"))
      (node (ref "C01F") (pin "-") (pinfunction "-_-") (pintype "passive"))
      (node (ref "C01O") (pin "2") (pinfunction "2_2") (pintype "passive"))
      (node (ref "C01R") (pin "2") (pinfunction "2_2") (pintype "passive"))
      (node (ref "C01S") (pin "2") (pinfunction "2_2") (pintype "passive"))
      (node (ref "C02D") (pin "1") (pinfunction "1_1") (pintype "passive"))
      (node (ref "C02I") (pin "2") (pinfunction "2_2") (pintype "passive"))
      (node (ref "C02R") (pin "-") (pinfunction "-_-") (pintype "passive"))
      (node (ref "C03R") (pin "2") (pinfunction "2_2") (pintype "passive"))
      (node (ref "C04R") (pin "-") (pinfunction "-_-") (pintype "passive"))
      (node (ref "C10D") (pin "2") (pinfunction "2_2") (pintype "passive"))
      (node (ref "C10R") (pin "2") (pinfunction "2_2") (pintype "passive"))
      (node (ref "C11D") (pin "2") (pinfunction "2_2") (pintype "passive"))
      (node (ref "C12D") (pin "2") (pinfunction "2_2") (pintype "passive"))
      (node (ref "C14A") (pin "2") (pinfunction "2_2") (pintype "passive"))
      (node (ref "C20W") (pin "2") (pinfunction "2_2") (pintype "passive"))
      (node (ref "C21W") (pin "2") (pinfunction "2_2") (pintype "passive"))
      (node (ref "C30A") (pin "1") (pinfunction "1_1") (pintype "passive"))
      (node (ref "C30D") (pin "2") (pinfunction "2_2") (pintype "passive"))
      (node (ref "C30I") (pin "1") (pinfunction "1_1") (pintype "passive"))
      (node (ref "C30P") (pin "2") (pinfunction "2_2") (pintype "passive"))
      (node (ref "C30R") (pin "2") (pinfunction "2_2") (pintype "passive"))
      (node (ref "C31D") (pin "2") (pinfunction "2_2") (pintype "passive"))
      (node (ref "C31R") (pin "2") (pinfunction "2_2") (pintype "passive"))
      (node (ref "C50D") (pin "2") (pinfunction "2_2") (pintype "passive"))
      (node (ref "C50L") (pin "2") (pinfunction "2_2") (pintype "passive"))
      (node (ref "C50S") (pin "2") (pinfunction "2_2") (pintype "passive"))
      (node (ref "C51L") (pin "2") (pinfunction "2_2") (pintype "passive"))
      (node (ref "C51S") (pin "2") (pinfunction "2_2") (pintype "passive"))
      (node (ref "C52L") (pin "2") (pinfunction "2_2") (pintype "passive"))
      (node (ref "C53L") (pin "2") (pinfunction "2_2") (pintype "passive"))
      (node (ref "CS1") (pin "2") (pinfunction "2_2") (pintype "passive"))
      (node (ref "CS2") (pin "2") (pinfunction "2_2") (pintype "passive"))
      (node (ref "DIS20") (pin "2") (pinfunction "2.GND_2") (pintype "passive"))
      (node (ref "GND1") (pin "1") (pinfunction "P$1_1") (pintype "passive"))
      (node (ref "GND2") (pin "1") (pinfunction "P$1_1") (pintype "passive"))
      (node (ref "J01I") (pin "2") (pinfunction "2_2") (pintype "passive"))
      (node (ref "J01O") (pin "2") (pinfunction "2_2") (pintype "passive"))
      (node (ref "J10P") (pin "3") (pinfunction "3_3") (pintype "passive"))
      (node (ref "J10U") (pin "3") (pinfunction "3_3") (pintype "passive"))
      (node (ref "J20T") (pin "2") (pinfunction "2_2") (pintype "passive"))
      (node (ref "J20T") (pin "4") (pinfunction "4_4") (pintype "passive"))
      (node (ref "J20T") (pin "6") (pinfunction "6_6") (pintype "passive"))
      (node (ref "J20T") (pin "8") (pinfunction "8_8") (pintype "passive"))
      (node (ref "J21T") (pin "2") (pinfunction "2_2") (pintype "passive"))
      (node (ref "J21T") (pin "4") (pinfunction "4_4") (pintype "passive"))
      (node (ref "J21T") (pin "6") (pinfunction "6_6") (pintype "passive"))
      (node (ref "J21T") (pin "8") (pinfunction "8_8") (pintype "passive"))
      (node (ref "J30E") (pin "2") (pinfunction "2_2") (pintype "passive"))
      (node (ref "J30P") (pin "2") (pinfunction "2_2") (pintype "passive"))
      (node (ref "J30S") (pin "4") (pinfunction "4_4") (pintype "passive"))
      (node (ref "J50L") (pin "3") (pinfunction "3_3") (pintype "passive"))
      (node (ref "LD10-R") (pin "C") (pinfunction "C_C") (pintype "passive"))
      (node (ref "LD11-G") (pin "C") (pinfunction "C_C") (pintype "passive"))
      (node (ref "LD50") (pin "5") (pinfunction "5.GND_5") (pintype "passive"))
      (node (ref "LD50R") (pin "C") (pinfunction "C_C") (pintype "passive"))
      (node (ref "LD51") (pin "5") (pinfunction "5.GND_5") (pintype "passive"))
      (node (ref "LD51R") (pin "C") (pinfunction "C_C") (pintype "passive"))
      (node (ref "LD52") (pin "5") (pinfunction "5.GND_5") (pintype "passive"))
      (node (ref "LD53") (pin "5") (pinfunction "5.GND_5") (pintype "passive"))
      (node (ref "R01O") (pin "1") (pinfunction "1_1") (pintype "passive"))
      (node (ref "R02R") (pin "2") (pinfunction "2_2") (pintype "passive"))
      (node (ref "R31B") (pin "2") (pinfunction "2_2") (pintype "passive"))
      (node (ref "R31I") (pin "2") (pinfunction "2_2") (pintype "passive"))
      (node (ref "R32A") (pin "2") (pinfunction "2_2") (pintype "passive"))
      (node (ref "R34A") (pin "2") (pinfunction "2_2") (pintype "passive"))
      (node (ref "R51S") (pin "2") (pinfunction "2_2") (pintype "passive"))
      (node (ref "R53S") (pin "2") (pinfunction "2_2") (pintype "passive"))
      (node (ref "RESET") (pin "2") (pinfunction "3-4_2") (pintype "passive"))
      (node (ref "RG01") (pin "1") (pinfunction "1.GND_1") (pintype "passive"))
      (node (ref "T50P") (pin "S") (pinfunction "S2_S") (pintype "bidirectional"))
      (node (ref "T51P") (pin "S") (pinfunction "S2_S") (pintype "bidirectional"))
      (node (ref "TOUCH1") (pin "2") (pinfunction "2_2") (pintype "passive"))
      (node (ref "TOUCH2") (pin "2") (pinfunction "2_2") (pintype "passive"))
      (node (ref "TOUCH3") (pin "2") (pinfunction "2_2") (pintype "passive"))
      (node (ref "TOUCH4") (pin "2") (pinfunction "2_2") (pintype "passive"))
      (node (ref "U01C") (pin "16") (pinfunction "16.SYNC_16") (pintype "passive"))
      (node (ref "U01C") (pin "17") (pinfunction "17.CELLS0_17") (pintype "passive"))
      (node (ref "U01C") (pin "23") (pinfunction "23.GND_23") (pintype "passive"))
      (node (ref "U01C") (pin "24") (pinfunction "24.GND_24") (pintype "passive"))
      (node (ref "U01C") (pin "29") (pinfunction "29.AGND_29") (pintype "passive"))
      (node (ref "U01C") (pin "V1") (pinfunction "29.AGND_V1") (pintype "passive"))
      (node (ref "U01C") (pin "V2") (pinfunction "29.AGND_V2") (pintype "passive"))
      (node (ref "U01C") (pin "V3") (pinfunction "29.AGND_V3") (pintype "passive"))
      (node (ref "U01C") (pin "V4") (pinfunction "29.AGND_V4") (pintype "passive"))
      (node (ref "U01S") (pin "1") (pinfunction "1.GND_1") (pintype "passive"))
      (node (ref "U10") (pin "23") (pinfunction "23.GND_23") (pintype "passive"))
      (node (ref "U10") (pin "35") (pinfunction "35.GND_35") (pintype "passive"))
      (node (ref "U10") (pin "44") (pinfunction "44.BOOT0_44") (pintype "passive"))
      (node (ref "U10") (pin "47") (pinfunction "47.GND_47") (pintype "passive"))
      (node (ref "U10") (pin "8") (pinfunction "8.GND_8") (pintype "passive"))
      (node (ref "U20W") (pin "1") (pinfunction "1.GND_1") (pintype "passive"))
      (node (ref "U20W") (pin "15") (pinfunction "15.GND_15") (pintype "passive"))
      (node (ref "U20W") (pin "38") (pinfunction "38.GND_38") (pintype "passive"))
      (node (ref "U20W") (pin "GND") (pinfunction "39.GND_GND") (pintype "passive"))
      (node (ref "U30A") (pin "2") (pinfunction "2.V-_2") (pintype "passive"))
      (node (ref "U30E") (pin "4") (pinfunction "4.V-_4") (pintype "passive"))
      (node (ref "U30R") (pin "2") (pinfunction "2.GND_2") (pintype "passive"))
      (node (ref "U31A") (pin "2") (pinfunction "2.V-_2") (pintype "passive"))
      (node (ref "U50L") (pin "1") (pinfunction "1.OE_1") (pintype "passive"))
      (node (ref "U50L") (pin "3") (pinfunction "3.GND_3") (pintype "passive"))
      (node (ref "Z10P") (pin "2") (pinfunction "A_2") (pintype "passive"))
      (node (ref "Z10U") (pin "2") (pinfunction "A_2") (pintype "passive"))
      (node (ref "Z11P") (pin "2") (pinfunction "A_2") (pintype "passive"))
      (node (ref "Z11U") (pin "2") (pinfunction "A_2") (pintype "passive"))
      (node (ref "Z30") (pin "1") (pinfunction "A_1") (pintype "passive"))
      (node (ref "Z31") (pin "1") (pinfunction "A_1") (pintype "passive"))
      (node (ref "Z32") (pin "1") (pinfunction "A_1") (pintype "passive"))
      (node (ref "Z50") (pin "1") (pinfunction "A_1") (pintype "passive"))
      (node (ref "Z50S") (pin "1") (pinfunction "A_1") (pintype "passive"))
      (node (ref "Z51") (pin "1") (pinfunction "A_1") (pintype "passive"))
      (node (ref "Z51S") (pin "1") (pinfunction "A_1") (pintype "passive"))
    )
    (net (code "16") (name "IBAT") (class "Default")
      (node (ref "U01S") (pin "3") (pinfunction "3.OUT_3") (pintype "passive"))
      (node (ref "U10") (pin "19") (pinfunction "19.PB1_19") (pintype "passive"))
    )
    (net (code "17") (name "LED_DIN") (class "Default")
      (node (ref "U10") (pin "28") (pinfunction "28.PB15_28") (pintype "passive"))
      (node (ref "U50L") (pin "2") (pinfunction "2.A_2") (pintype "passive"))
    )
    (net (code "18") (name "LED_GRN") (class "Default")
      (node (ref "GRN") (pin "1") (pinfunction "P$1_1") (pintype "passive"))
      (node (ref "R11L") (pin "1") (pinfunction "1_1") (pintype "passive"))
      (node (ref "U10") (pin "6") (pinfunction "6.OSC_OUT_6") (pintype "passive"))
    )
    (net (code "19") (name "LED_OUT") (class "Default")
      (node (ref "J50L") (pin "2") (pinfunction "2_2") (pintype "passive"))
      (node (ref "LD53") (pin "3") (pinfunction "3.DO_3") (pintype "passive"))
    )
    (net (code "20") (name "LED_RED") (class "Default")
      (node (ref "R10L") (pin "1") (pinfunction "1_1") (pintype "passive"))
      (node (ref "RED") (pin "1") (pinfunction "P$1_1") (pintype "passive"))
      (node (ref "U10") (pin "5") (pinfunction "5.OSC_IN_5") (pintype "passive"))
    )
    (net (code "21") (name "Net-(C01F-Pad+)") (class "Default")
      (node (ref "C01F") (pin "+") (pinfunction "+_+") (pintype "passive"))
      (node (ref "R01F") (pin "2") (pinfunction "2_2") (pintype "passive"))
    )
    (net (code "22") (name "Net-(D50-+)") (class "Default")
      (node (ref "D50") (pin "2") (pinfunction "+_2") (pintype "passive"))
      (node (ref "J50") (pin "3") (pinfunction "3_3") (pintype "passive"))
      (node (ref "T50P") (pin "D") (pinfunction "D3_D") (pintype "bidirectional"))
      (node (ref "Z50") (pin "2") (pinfunction "C_2") (pintype "passive"))
    )
    (net (code "23") (name "Net-(D50S-+)") (class "Default")
      (node (ref "D50S") (pin "2") (pinfunction "+_2") (pintype "passive"))
      (node (ref "J50") (pin "2") (pinfunction "2_2") (pintype "passive"))
    )
    (net (code "24") (name "Net-(D50S--)") (class "Default")
      (node (ref "C50S") (pin "1") (pinfunction "1_1") (pintype "passive"))
      (node (ref "D50S") (pin "1-") (pinfunction "-_1-") (pintype "passive"))
      (node (ref "R50S") (pin "2") (pinfunction "2_2") (pintype "passive"))
    )
    (net (code "25") (name "Net-(D51-+)") (class "Default")
      (node (ref "D51") (pin "2") (pinfunction "+_2") (pintype "passive"))
      (node (ref "J51") (pin "3") (pinfunction "3_3") (pintype "passive"))
      (node (ref "T51P") (pin "D") (pinfunction "D3_D") (pintype "bidirectional"))
      (node (ref "Z51") (pin "2") (pinfunction "C_2") (pintype "passive"))
    )
    (net (code "26") (name "Net-(D51S-+)") (class "Default")
      (node (ref "D51S") (pin "2") (pinfunction "+_2") (pintype "passive"))
      (node (ref "J51") (pin "2") (pinfunction "2_2") (pintype "passive"))
    )
    (net (code "27") (name "Net-(D51S--)") (class "Default")
      (node (ref "C51S") (pin "1") (pinfunction "1_1") (pintype "passive"))
      (node (ref "D51S") (pin "1-") (pinfunction "-_1-") (pintype "passive"))
      (node (ref "R52S") (pin "2") (pinfunction "2_2") (pintype "passive"))
    )
    (net (code "28") (name "Net-(F20S-P$1)") (class "Default")
      (node (ref "F20S") (pin "1") (pinfunction "P$1_1") (pintype "passive"))
      (node (ref "J50L") (pin "1") (pinfunction "1_1") (pintype "passive"))
    )
    (net (code "29") (name "Net-(LD10-R-PadA)") (class "Default")
      (node (ref "LD10-R") (pin "A") (pinfunction "A_A") (pintype "passive"))
      (node (ref "R10L") (pin "2") (pinfunction "2_2") (pintype "passive"))
    )
    (net (code "30") (name "Net-(LD11-G-PadA)") (class "Default")
      (node (ref "LD11-G") (pin "A") (pinfunction "A_A") (pintype "passive"))
      (node (ref "R11L") (pin "2") (pinfunction "2_2") (pintype "passive"))
    )
    (net (code "31") (name "Net-(LD50-1.VCC)") (class "Default")
      (node (ref "C50L") (pin "1") (pinfunction "1_1") (pintype "passive"))
      (node (ref "LD50") (pin "1") (pinfunction "1.VCC_1") (pintype "passive"))
    )
    (net (code "32") (name "Net-(LD50-3.DO)") (class "Default")
      (node (ref "LD50") (pin "3") (pinfunction "3.DO_3") (pintype "passive"))
      (node (ref "LD51") (pin "4") (pinfunction "4.DIN_4") (pintype "passive"))
    )
    (net (code "33") (name "Net-(LD50-4.DIN)") (class "Default")
      (node (ref "LD50") (pin "4") (pinfunction "4.DIN_4") (pintype "passive"))
      (node (ref "U50L") (pin "4") (pinfunction "4.Y_4") (pintype "passive"))
    )
    (net (code "34") (name "Net-(LD50R-PadA)") (class "Default")
      (node (ref "LD50R") (pin "A") (pinfunction "A_A") (pintype "passive"))
      (node (ref "R50L") (pin "2") (pinfunction "2_2") (pintype "passive"))
    )
    (net (code "35") (name "Net-(LD51-1.VCC)") (class "Default")
      (node (ref "C51L") (pin "1") (pinfunction "1_1") (pintype "passive"))
      (node (ref "LD51") (pin "1") (pinfunction "1.VCC_1") (pintype "passive"))
    )
    (net (code "36") (name "Net-(LD51-3.DO)") (class "Default")
      (node (ref "LD51") (pin "3") (pinfunction "3.DO_3") (pintype "passive"))
      (node (ref "LD52") (pin "4") (pinfunction "4.DIN_4") (pintype "passive"))
    )
    (net (code "37") (name "Net-(LD51R-PadA)") (class "Default")
      (node (ref "LD51R") (pin "A") (pinfunction "A_A") (pintype "passive"))
      (node (ref "R51L") (pin "2") (pinfunction "2_2") (pintype "passive"))
    )
    (net (code "38") (name "Net-(LD52-1.VCC)") (class "Default")
      (node (ref "C52L") (pin "1") (pinfunction "1_1") (pintype "passive"))
      (node (ref "LD52") (pin "1") (pinfunction "1.VCC_1") (pintype "passive"))
    )
    (net (code "39") (name "Net-(LD52-3.DO)") (class "Default")
      (node (ref "LD52") (pin "3") (pinfunction "3.DO_3") (pintype "passive"))
      (node (ref "LD53") (pin "4") (pinfunction "4.DIN_4") (pintype "passive"))
    )
    (net (code "40") (name "Net-(LD53-1.VCC)") (class "Default")
      (node (ref "C53L") (pin "1") (pinfunction "1_1") (pintype "passive"))
      (node (ref "LD53") (pin "1") (pinfunction "1.VCC_1") (pintype "passive"))
    )
    (net (code "41") (name "Net-(RG02-1.GND)") (class "Default")
      (node (ref "R01R") (pin "2") (pinfunction "2_2") (pintype "passive"))
      (node (ref "R02R") (pin "1") (pinfunction "1_1") (pintype "passive"))
      (node (ref "RG02") (pin "1") (pinfunction "1.GND_1") (pintype "passive"))
    )
    (net (code "42") (name "Net-(T01P-D3)") (class "Default")
      (node (ref "R01P") (pin "1") (pinfunction "1_1") (pintype "passive"))
      (node (ref "T01P") (pin "D") (pinfunction "D3_D") (pintype "bidirectional"))
    )
    (net (code "43") (name "Net-(T01P-G1)") (class "Default")
      (node (ref "T01P") (pin "G") (pinfunction "G1_G") (pintype "bidirectional"))
      (node (ref "U01C") (pin "6") (pinfunction "6.INFET_6") (pintype "passive"))
    )
    (net (code "44") (name "Net-(T02P-G1)") (class "Default")
      (node (ref "T02P") (pin "G") (pinfunction "G1_G") (pintype "bidirectional"))
      (node (ref "U01C") (pin "22") (pinfunction "22.BATFET_22") (pintype "passive"))
    )
    (net (code "45") (name "Net-(T02P-S2)") (class "Default")
      (node (ref "L01P") (pin "2") (pinfunction "2_2") (pintype "passive"))
      (node (ref "R02P") (pin "2") (pinfunction "2_2") (pintype "passive"))
      (node (ref "T02P") (pin "S") (pinfunction "S2_S") (pintype "bidirectional"))
    )
    (net (code "46") (name "Net-(U01C-1.BOOST)") (class "Default")
      (node (ref "C01B") (pin "1") (pinfunction "1_1") (pintype "passive"))
      (node (ref "U01C") (pin "1") (pinfunction "1.BOOST_1") (pintype "passive"))
    )
    (net (code "47") (name "Net-(U01C-4.CLN)") (class "Default")
      (node (ref "R01P") (pin "4") (pinfunction "4_4") (pintype "passive"))
      (node (ref "U01C") (pin "4") (pinfunction "4.CLN_4") (pintype "passive"))
    )
    (net (code "48") (name "Net-(U01C-5.CLP)") (class "Default")
      (node (ref "R01P") (pin "3") (pinfunction "3_3") (pintype "passive"))
      (node (ref "U01C") (pin "5") (pinfunction "5.CLP_5") (pintype "passive"))
    )
    (net (code "49") (name "Net-(U01C-8.VCC2P5)") (class "Default")
      (node (ref "C01D") (pin "2") (pinfunction "2_2") (pintype "passive"))
      (node (ref "U01C") (pin "8") (pinfunction "8.VCC2P5_8") (pintype "passive"))
    )
    (net (code "50") (name "Net-(U01C-11.RT)") (class "Default")
      (node (ref "R01O") (pin "2") (pinfunction "2_2") (pintype "passive"))
      (node (ref "U01C") (pin "11") (pinfunction "11.RT_11") (pintype "passive"))
    )
    (net (code "51") (name "Net-(U01C-18.CELLS1)") (class "Default")
      (node (ref "C02D") (pin "2") (pinfunction "2_2") (pintype "passive"))
      (node (ref "U01C") (pin "18") (pinfunction "18.CELLS1_18") (pintype "passive"))
      (node (ref "U01C") (pin "2") (pinfunction "2.INTVCC_2") (pintype "passive"))
    )
    (net (code "52") (name "Net-(U01C-19.BATSENS+)") (class "Default")
      (node (ref "R01S") (pin "1") (pinfunction "1_1") (pintype "passive"))
      (node (ref "R02P") (pin "1") (pinfunction "1_1") (pintype "passive"))
      (node (ref "U01C") (pin "19") (pinfunction "19.BATSENS+_19") (pintype "passive"))
      (node (ref "U01S") (pin "6") (pinfunction "6.RS+_6") (pintype "passive"))
    )
    (net (code "53") (name "Net-(U01C-20.CSN)") (class "Default")
      (node (ref "R02P") (pin "3") (pinfunction "3_3") (pintype "passive"))
      (node (ref "U01C") (pin "20") (pinfunction "20.CSN_20") (pintype "passive"))
    )
    (net (code "54") (name "Net-(U01C-21.CSP)") (class "Default")
      (node (ref "R02P") (pin "4") (pinfunction "4_4") (pintype "passive"))
      (node (ref "U01C") (pin "21") (pinfunction "21.CSP_21") (pintype "passive"))
    )
    (net (code "55") (name "Net-(U01C-25.SW)") (class "Default")
      (node (ref "C01B") (pin "2") (pinfunction "2_2") (pintype "passive"))
      (node (ref "L01P") (pin "1") (pinfunction "1_1") (pintype "passive"))
      (node (ref "U01C") (pin "25") (pinfunction "25.SW_25") (pintype "passive"))
      (node (ref "U01C") (pin "26") (pinfunction "26.SW_26") (pintype "passive"))
    )
    (net (code "56") (name "Net-(U10-9.VDD)") (class "Default")
      (node (ref "C14A") (pin "1") (pinfunction "1_1") (pintype "passive"))
      (node (ref "L10A") (pin "2") (pinfunction "2_2") (pintype "passive"))
      (node (ref "U10") (pin "9") (pinfunction "9.VDD_9") (pintype "passive"))
    )
    (net (code "57") (name "Net-(U10-25.PB12)") (class "Default")
      (node (ref "CS2") (pin "1") (pinfunction "1_1") (pintype "passive"))
      (node (ref "U10") (pin "25") (pinfunction "25.PB12_25") (pintype "passive"))
    )
    (net (code "58") (name "Net-(U10-40.PB4)") (class "Default")
      (node (ref "CS1") (pin "1") (pinfunction "1_1") (pintype "passive"))
      (node (ref "U10") (pin "40") (pinfunction "40.PB4_40") (pintype "passive"))
    )
    (net (code "59") (name "Net-(U30A-1.OUT)") (class "Default")
      (node (ref "C31A") (pin "1") (pinfunction "1_1") (pintype "passive"))
      (node (ref "R31A") (pin "2") (pinfunction "2_2") (pintype "passive"))
      (node (ref "U30A") (pin "1") (pinfunction "1.OUT_1") (pintype "passive"))
      (node (ref "U31A") (pin "3") (pinfunction "3.IN+_3") (pintype "passive"))
    )
    (net (code "60") (name "Net-(U30A-3.IN+)") (class "Default")
      (node (ref "C30A") (pin "2") (pinfunction "2_2") (pintype "passive"))
      (node (ref "R30A") (pin "2") (pinfunction "2_2") (pintype "passive"))
      (node (ref "U30A") (pin "3") (pinfunction "3.IN+_3") (pintype "passive"))
    )
    (net (code "61") (name "Net-(U30A-4.IN-)") (class "Default")
      (node (ref "C31A") (pin "2") (pinfunction "2_2") (pintype "passive"))
      (node (ref "R31A") (pin "1") (pinfunction "1_1") (pintype "passive"))
      (node (ref "R32A") (pin "1") (pinfunction "1_1") (pintype "passive"))
      (node (ref "U30A") (pin "4") (pinfunction "4.IN-_4") (pintype "passive"))
    )
    (net (code "62") (name "Net-(U30A-5.~{SHDN})") (class "Default")
      (node (ref "C30D") (pin "1") (pinfunction "1_1") (pintype "passive"))
      (node (ref "L30D") (pin "2") (pinfunction "2_2") (pintype "passive"))
      (node (ref "U30A") (pin "5") (pinfunction "5.~{SHDN}_5") (pintype "passive"))
      (node (ref "U30A") (pin "6") (pinfunction "6.V+_6") (pintype "passive"))
    )
    (net (code "63") (name "Net-(U30EA-1.OUT)") (class "Default")
      (node (ref "R30O") (pin "2") (pinfunction "2_2") (pintype "passive"))
      (node (ref "U30E") (pin "1") (pinfunction "1.OUT_1") (pintype "passive"))
      (node (ref "U30E") (pin "2") (pinfunction "2.IN-_2") (pintype "passive"))
    )
    (net (code "64") (name "Net-(U30EB-5.IN+)") (class "Default")
      (node (ref "C30I") (pin "2") (pinfunction "2_2") (pintype "passive"))
      (node (ref "R30I") (pin "2") (pinfunction "2_2") (pintype "passive"))
      (node (ref "R31I") (pin "1") (pinfunction "1_1") (pintype "passive"))
      (node (ref "U30E") (pin "5") (pinfunction "5.IN+_5") (pintype "passive"))
    )
    (net (code "65") (name "Net-(U31A-4.IN-)") (class "Default")
      (node (ref "C32A") (pin "2") (pinfunction "2_2") (pintype "passive"))
      (node (ref "R33A") (pin "1") (pinfunction "1_1") (pintype "passive"))
      (node (ref "R34A") (pin "1") (pinfunction "1_1") (pintype "passive"))
      (node (ref "U31A") (pin "4") (pinfunction "4.IN-_4") (pintype "passive"))
    )
    (net (code "66") (name "Net-(U31A-5.~{SHDN})") (class "Default")
      (node (ref "C31D") (pin "1") (pinfunction "1_1") (pintype "passive"))
      (node (ref "L31D") (pin "2") (pinfunction "2_2") (pintype "passive"))
      (node (ref "U31A") (pin "5") (pinfunction "5.~{SHDN}_5") (pintype "passive"))
      (node (ref "U31A") (pin "6") (pinfunction "6.V+_6") (pintype "passive"))
    )
    (net (code "67") (name "OLED_CD") (class "Default")
      (node (ref "DIS20") (pin "6") (pinfunction "6.DC_6") (pintype "passive"))
      (node (ref "U10") (pin "33") (pinfunction "33.PA12_33") (pintype "passive"))
    )
    (net (code "68") (name "OLED_CS") (class "Default")
      (node (ref "DIS20") (pin "5") (pinfunction "5.CS_5") (pintype "passive"))
      (node (ref "U10") (pin "32") (pinfunction "32.PA11_32") (pintype "passive"))
    )
    (net (code "69") (name "OLED_MOSI") (class "Default")
      (node (ref "DIS20") (pin "3") (pinfunction "3.DIN_3") (pintype "passive"))
      (node (ref "U10") (pin "17") (pinfunction "17.PA7_17") (pintype "passive"))
    )
    (net (code "70") (name "OLED_SCK") (class "Default")
      (node (ref "DIS20") (pin "4") (pinfunction "4.CLK_4") (pintype "passive"))
      (node (ref "U10") (pin "15") (pinfunction "15.PA5_15") (pintype "passive"))
    )
    (net (code "71") (name "PAR") (class "Default")
      (node (ref "C32A") (pin "1") (pinfunction "1_1") (pintype "passive"))
      (node (ref "R33A") (pin "2") (pinfunction "2_2") (pintype "passive"))
      (node (ref "U10") (pin "10") (pinfunction "10.PA0_10") (pintype "passive"))
      (node (ref "U31A") (pin "1") (pinfunction "1.OUT_1") (pintype "passive"))
    )
    (net (code "72") (name "PAR_IN") (class "Default")
      (node (ref "J30P") (pin "1") (pinfunction "1_1") (pintype "passive"))
      (node (ref "R30A") (pin "1") (pinfunction "1_1") (pintype "passive"))
    )
    (net (code "73") (name "PUMP0") (class "Default")
      (node (ref "R50L") (pin "1") (pinfunction "1_1") (pintype "passive"))
      (node (ref "T50P") (pin "G") (pinfunction "G1_G") (pintype "bidirectional"))
      (node (ref "U10") (pin "18") (pinfunction "18.PB0_18") (pintype "passive"))
    )
    (net (code "74") (name "PUMP1") (class "Default")
      (node (ref "R51L") (pin "1") (pinfunction "1_1") (pintype "passive"))
      (node (ref "T51P") (pin "G") (pinfunction "G1_G") (pintype "bidirectional"))
      (node (ref "U10") (pin "39") (pinfunction "39.PB3_39") (pintype "passive"))
    )
    (net (code "75") (name "REF_EC") (class "Default")
      (node (ref "U10") (pin "38") (pinfunction "38.PA15_38") (pintype "passive"))
      (node (ref "U30R") (pin "3") (pinfunction "3.ENA_3") (pintype "passive"))
    )
    (net (code "76") (name "SCL") (class "Default")
      (node (ref "R10P") (pin "1") (pinfunction "1_1") (pintype "passive"))
      (node (ref "U01C") (pin "13") (pinfunction "13.SCL_13") (pintype "passive"))
      (node (ref "U10") (pin "45") (pinfunction "45.PB8_45") (pintype "passive"))
    )
    (net (code "77") (name "SDA") (class "Default")
      (node (ref "R11P") (pin "1") (pinfunction "1_1") (pintype "passive"))
      (node (ref "U01C") (pin "14") (pinfunction "14.SDA_14") (pintype "passive"))
      (node (ref "U10") (pin "46") (pinfunction "46.PB9_46") (pintype "passive"))
    )
    (net (code "78") (name "SER_RXD") (class "Default")
      (node (ref "J10U") (pin "1") (pinfunction "1_1") (pintype "passive"))
      (node (ref "U10") (pin "13") (pinfunction "13.PA3_13") (pintype "passive"))
      (node (ref "Z11U") (pin "1") (pinfunction "C_1") (pintype "passive"))
    )
    (net (code "79") (name "SER_TXD") (class "Default")
      (node (ref "J10U") (pin "2") (pinfunction "2_2") (pintype "passive"))
      (node (ref "U10") (pin "12") (pinfunction "12.PA2_12") (pintype "passive"))
      (node (ref "Z10U") (pin "1") (pinfunction "C_1") (pintype "passive"))
    )
    (net (code "80") (name "SHT_CLK") (class "Default")
      (node (ref "J30S") (pin "3") (pinfunction "3_3") (pintype "passive"))
      (node (ref "U10") (pin "30") (pinfunction "30.PA9_30") (pintype "passive"))
    )
    (net (code "81") (name "SHT_DAT") (class "Default")
      (node (ref "J30S") (pin "2") (pinfunction "2_2") (pintype "passive"))
      (node (ref "R30S") (pin "2") (pinfunction "2_2") (pintype "passive"))
      (node (ref "U10") (pin "29") (pinfunction "29.PA8_29") (pintype "passive"))
    )
    (net (code "82") (name "SPEED0") (class "Default")
      (node (ref "R50S") (pin "1") (pinfunction "1_1") (pintype "passive"))
      (node (ref "R51S") (pin "1") (pinfunction "1_1") (pintype "passive"))
      (node (ref "U10") (pin "2") (pinfunction "2.PC13_2") (pintype "passive"))
      (node (ref "Z50S") (pin "2") (pinfunction "C_2") (pintype "passive"))
    )
    (net (code "83") (name "SPEED1") (class "Default")
      (node (ref "R52S") (pin "1") (pinfunction "1_1") (pintype "passive"))
      (node (ref "R53S") (pin "1") (pinfunction "1_1") (pintype "passive"))
      (node (ref "U10") (pin "3") (pinfunction "3.PC14_3") (pintype "passive"))
      (node (ref "Z51S") (pin "2") (pinfunction "C_2") (pintype "passive"))
    )
    (net (code "84") (name "SWD_CLK") (class "Default")
      (node (ref "J10P") (pin "2") (pinfunction "2_2") (pintype "passive"))
      (node (ref "U10") (pin "37") (pinfunction "37.PA14_37") (pintype "passive"))
      (node (ref "Z11P") (pin "1") (pinfunction "C_1") (pintype "passive"))
    )
    (net (code "85") (name "SWD_IO") (class "Default")
      (node (ref "J10P") (pin "1") (pinfunction "1_1") (pintype "passive"))
      (node (ref "U10") (pin "34") (pinfunction "34.PA13_34") (pintype "passive"))
      (node (ref "Z10P") (pin "1") (pinfunction "C_1") (pintype "passive"))
    )
    (net (code "86") (name "V0") (class "Default")
      (node (ref "C30P") (pin "1") (pinfunction "1_1") (pintype "passive"))
      (node (ref "L30P") (pin "2") (pinfunction "2_2") (pintype "passive"))
      (node (ref "R30B") (pin "1") (pinfunction "1_1") (pintype "passive"))
      (node (ref "R30C") (pin "1") (pinfunction "1_1") (pintype "passive"))
      (node (ref "R30I") (pin "1") (pinfunction "1_1") (pintype "passive"))
      (node (ref "U30E") (pin "8") (pinfunction "8.V+_8") (pintype "passive"))
    )
    (net (code "87") (name "VCC") (class "Default")
      (node (ref "C04R") (pin "+") (pinfunction "+_+") (pintype "passive"))
      (node (ref "C50D") (pin "1") (pinfunction "1_1") (pintype "passive"))
      (node (ref "R01R") (pin "1") (pinfunction "1_1") (pintype "passive"))
      (node (ref "RG02") (pin "2") (pinfunction "2.OUT_2") (pintype "passive"))
      (node (ref "RG02") (pin "4") (pinfunction "4.OUT_4") (pintype "passive"))
      (node (ref "U50L") (pin "5") (pinfunction "5.VDD_5") (pintype "passive"))
    )
    (net (code "88") (name "VCCA") (class "Default")
      (node (ref "C31R") (pin "1") (pinfunction "1_1") (pintype "passive"))
      (node (ref "L30P") (pin "1") (pinfunction "1_1") (pintype "passive"))
      (node (ref "U30R") (pin "5") (pinfunction "5.VOUT_5") (pintype "passive"))
    )
    (net (code "89") (name "VDD_3V3") (class "Default")
      (node (ref "C01S") (pin "1") (pinfunction "1_1") (pintype "passive"))
      (node (ref "C02R") (pin "+") (pinfunction "+_+") (pintype "passive"))
      (node (ref "C10D") (pin "1") (pinfunction "1_1") (pintype "passive"))
      (node (ref "C11D") (pin "1") (pinfunction "1_1") (pintype "passive"))
      (node (ref "C12D") (pin "1") (pinfunction "1_1") (pintype "passive"))
      (node (ref "C20W") (pin "1") (pinfunction "1_1") (pintype "passive"))
      (node (ref "C21W") (pin "1") (pinfunction "1_1") (pintype "passive"))
      (node (ref "C30R") (pin "1") (pinfunction "1_1") (pintype "passive"))
      (node (ref "DIS20") (pin "1") (pinfunction "1.VCC_1") (pintype "passive"))
      (node (ref "L10A") (pin "1") (pinfunction "1_1") (pintype "passive"))
      (node (ref "L30D") (pin "1") (pinfunction "1_1") (pintype "passive"))
      (node (ref "L31D") (pin "1") (pinfunction "1_1") (pintype "passive"))
      (node (ref "R10P") (pin "2") (pinfunction "2_2") (pintype "passive"))
      (node (ref "R11P") (pin "2") (pinfunction "2_2") (pintype "passive"))
      (node (ref "R12P") (pin "2") (pinfunction "2_2") (pintype "passive"))
      (node (ref "R20R") (pin "1") (pinfunction "1_1") (pintype "passive"))
      (node (ref "R30P") (pin "1") (pinfunction "1_1") (pintype "passive"))
      (node (ref "RG01") (pin "3") (pinfunction "3.OUT_3") (pintype "passive"))
      (node (ref "T30P") (pin "2") (pinfunction "S_2") (pintype "bidirectional"))
      (node (ref "U01C") (pin "15") (pinfunction "15.DVCC_15") (pintype "passive"))
      (node (ref "U01S") (pin "5") (pinfunction "5.VDD_5") (pintype "passive"))
      (node (ref "U10") (pin "24") (pinfunction "24.VDD_24") (pintype "passive"))
      (node (ref "U10") (pin "36") (pinfunction "36.VDD_36") (pintype "passive"))
      (node (ref "U10") (pin "48") (pinfunction "48.VDD_48") (pintype "passive"))
      (node (ref "U20W") (pin "2") (pinfunction "2.3V3_2") (pintype "passive"))
      (node (ref "U30R") (pin "4") (pinfunction "4.VIN_4") (pintype "passive"))
    )
    (net (code "90") (name "VOUT") (class "Default")
      (node (ref "C01O") (pin "1") (pinfunction "1_1") (pintype "passive"))
      (node (ref "R01P") (pin "2") (pinfunction "2_2") (pintype "passive"))
      (node (ref "T02P") (pin "D") (pinfunction "D3_D") (pintype "bidirectional"))
      (node (ref "U01C") (pin "27") (pinfunction "27.VOUT_27") (pintype "passive"))
      (node (ref "U01C") (pin "28") (pinfunction "28.VOUT_28") (pintype "passive"))
      (node (ref "U01C") (pin "3") (pinfunction "3.VOUTA_3") (pintype "passive"))
    )
    (net (code "91") (name "VSUN") (class "Default")
      (node (ref "C02I") (pin "1") (pinfunction "1_1") (pintype "passive"))
      (node (ref "J01I") (pin "1") (pinfunction "1_1") (pintype "passive"))
      (node (ref "R01F") (pin "1") (pinfunction "1_1") (pintype "passive"))
      (node (ref "T01P") (pin "S") (pinfunction "S2_S") (pintype "bidirectional"))
      (node (ref "U01C") (pin "7") (pinfunction "7.VIN_7") (pintype "passive"))
    )
    (net (code "92") (name "VY") (class "Default")
      (node (ref "J30S") (pin "1") (pinfunction "1_1") (pintype "passive"))
      (node (ref "R30S") (pin "1") (pinfunction "1_1") (pintype "passive"))
      (node (ref "T30P") (pin "3") (pinfunction "D_3") (pintype "bidirectional"))
    )
    (net (code "93") (name "WIFI_EN") (class "Default")
      (node (ref "U10") (pin "27") (pinfunction "27.PB14_27") (pintype "passive"))
      (node (ref "U20W") (pin "3") (pinfunction "3.EN_3") (pintype "passive"))
    )
    (net (code "94") (name "WIFI_RXD") (class "Default")
      (node (ref "U10") (pin "22") (pinfunction "22.PB11_22") (pintype "passive"))
      (node (ref "U20W") (pin "35") (pinfunction "35.TXD0_35") (pintype "passive"))
    )
    (net (code "95") (name "WIFI_TXD") (class "Default")
      (node (ref "U10") (pin "21") (pinfunction "21.PB10_21") (pintype "passive"))
      (node (ref "U20W") (pin "34") (pinfunction "34.RXD0_34") (pintype "passive"))
    )
    (net (code "96") (name "unconnected-(LD50-6.BIN-Pad6)") (class "Default")
      (node (ref "LD50") (pin "6") (pinfunction "6.BIN_6") (pintype "passive"))
    )
    (net (code "97") (name "unconnected-(LD51-6.BIN-Pad6)") (class "Default")
      (node (ref "LD51") (pin "6") (pinfunction "6.BIN_6") (pintype "passive"))
    )
    (net (code "98") (name "unconnected-(LD52-6.BIN-Pad6)") (class "Default")
      (node (ref "LD52") (pin "6") (pinfunction "6.BIN_6") (pintype "passive"))
    )
    (net (code "99") (name "unconnected-(LD53-6.BIN-Pad6)") (class "Default")
      (node (ref "LD53") (pin "6") (pinfunction "6.BIN_6") (pintype "passive"))
    )
    (net (code "100") (name "unconnected-(U01C-9.NTCBIAS-Pad9)") (class "Default")
      (node (ref "U01C") (pin "9") (pinfunction "9.NTCBIAS_9") (pintype "passive"))
    )
    (net (code "101") (name "unconnected-(U01C-10.NTC-Pad10)") (class "Default")
      (node (ref "U01C") (pin "10") (pinfunction "10.NTC_10") (pintype "passive"))
    )
    (net (code "102") (name "unconnected-(U01S-2.SIGN-Pad2)") (class "Default")
      (node (ref "U01S") (pin "2") (pinfunction "2.SIGN_2") (pintype "passive"))
    )
    (net (code "103") (name "unconnected-(U10-1.VDD-Pad1)") (class "Default")
      (node (ref "U10") (pin "1") (pinfunction "1.VDD_1") (pintype "passive"))
    )
    (net (code "104") (name "unconnected-(U10-4.PC15-Pad4)") (class "Default")
      (node (ref "U10") (pin "4") (pinfunction "4.PC15_4") (pintype "passive"))
    )
    (net (code "105") (name "unconnected-(U20W-4.SENSOR_VP-Pad4)") (class "Default")
      (node (ref "U20W") (pin "4") (pinfunction "4.SENSOR_VP_4") (pintype "passive"))
    )
    (net (code "106") (name "unconnected-(U20W-5.SENSOR_VN-Pad5)") (class "Default")
      (node (ref "U20W") (pin "5") (pinfunction "5.SENSOR_VN_5") (pintype "passive"))
    )
    (net (code "107") (name "unconnected-(U20W-6.IO34-Pad6)") (class "Default")
      (node (ref "U20W") (pin "6") (pinfunction "6.IO34_6") (pintype "passive"))
    )
    (net (code "108") (name "unconnected-(U20W-7.IO35-Pad7)") (class "Default")
      (node (ref "U20W") (pin "7") (pinfunction "7.IO35_7") (pintype "passive"))
    )
    (net (code "109") (name "unconnected-(U20W-8.IO32-Pad8)") (class "Default")
      (node (ref "U20W") (pin "8") (pinfunction "8.IO32_8") (pintype "passive"))
    )
    (net (code "110") (name "unconnected-(U20W-9.IO33-Pad9)") (class "Default")
      (node (ref "U20W") (pin "9") (pinfunction "9.IO33_9") (pintype "passive"))
    )
    (net (code "111") (name "unconnected-(U20W-10.IO25-Pad10)") (class "Default")
      (node (ref "U20W") (pin "10") (pinfunction "10.IO25_10") (pintype "passive"))
    )
    (net (code "112") (name "unconnected-(U20W-11.IO26-Pad11)") (class "Default")
      (node (ref "U20W") (pin "11") (pinfunction "11.IO26_11") (pintype "passive"))
    )
    (net (code "113") (name "unconnected-(U20W-12.IO27-Pad12)") (class "Default")
      (node (ref "U20W") (pin "12") (pinfunction "12.IO27_12") (pintype "passive"))
    )
    (net (code "114") (name "unconnected-(U20W-13.IO14-Pad13)") (class "Default")
      (node (ref "U20W") (pin "13") (pinfunction "13.IO14_13") (pintype "passive"))
    )
    (net (code "115") (name "unconnected-(U20W-14.IO12-Pad14)") (class "Default")
      (node (ref "U20W") (pin "14") (pinfunction "14.IO12_14") (pintype "passive"))
    )
    (net (code "116") (name "unconnected-(U20W-16.IO13-Pad16)") (class "Default")
      (node (ref "U20W") (pin "16") (pinfunction "16.IO13_16") (pintype "passive"))
    )
    (net (code "117") (name "unconnected-(U20W-17.SD2-Pad17)") (class "Default")
      (node (ref "U20W") (pin "17") (pinfunction "17.SD2_17") (pintype "passive"))
    )
    (net (code "118") (name "unconnected-(U20W-18.SD3-Pad18)") (class "Default")
      (node (ref "U20W") (pin "18") (pinfunction "18.SD3_18") (pintype "passive"))
    )
    (net (code "119") (name "unconnected-(U20W-19.CMD-Pad19)") (class "Default")
      (node (ref "U20W") (pin "19") (pinfunction "19.CMD_19") (pintype "passive"))
    )
    (net (code "120") (name "unconnected-(U20W-20.CLK-Pad20)") (class "Default")
      (node (ref "U20W") (pin "20") (pinfunction "20.CLK_20") (pintype "passive"))
    )
    (net (code "121") (name "unconnected-(U20W-21.SDO-Pad21)") (class "Default")
      (node (ref "U20W") (pin "21") (pinfunction "21.SDO_21") (pintype "passive"))
    )
    (net (code "122") (name "unconnected-(U20W-22.SD1-Pad22)") (class "Default")
      (node (ref "U20W") (pin "22") (pinfunction "22.SD1_22") (pintype "passive"))
    )
    (net (code "123") (name "unconnected-(U20W-23.IO15-Pad23)") (class "Default")
      (node (ref "U20W") (pin "23") (pinfunction "23.IO15_23") (pintype "passive"))
    )
    (net (code "124") (name "unconnected-(U20W-24.IO2-Pad24)") (class "Default")
      (node (ref "U20W") (pin "24") (pinfunction "24.IO2_24") (pintype "passive"))
    )
    (net (code "125") (name "unconnected-(U20W-25.IO0-Pad25)") (class "Default")
      (node (ref "U20W") (pin "25") (pinfunction "25.IO0_25") (pintype "passive"))
    )
    (net (code "126") (name "unconnected-(U20W-26.IO4-Pad26)") (class "Default")
      (node (ref "U20W") (pin "26") (pinfunction "26.IO4_26") (pintype "passive"))
    )
    (net (code "127") (name "unconnected-(U20W-27.IO16-Pad27)") (class "Default")
      (node (ref "U20W") (pin "27") (pinfunction "27.IO16_27") (pintype "passive"))
    )
    (net (code "128") (name "unconnected-(U20W-28.IO17-Pad28)") (class "Default")
      (node (ref "U20W") (pin "28") (pinfunction "28.IO17_28") (pintype "passive"))
    )
    (net (code "129") (name "unconnected-(U20W-29.IO5-Pad29)") (class "Default")
      (node (ref "U20W") (pin "29") (pinfunction "29.IO5_29") (pintype "passive"))
    )
    (net (code "130") (name "unconnected-(U20W-30.IO18-Pad30)") (class "Default")
      (node (ref "U20W") (pin "30") (pinfunction "30.IO18_30") (pintype "passive"))
    )
    (net (code "131") (name "unconnected-(U20W-31.IO19-Pad31)") (class "Default")
      (node (ref "U20W") (pin "31") (pinfunction "31.IO19_31") (pintype "passive"))
    )
    (net (code "132") (name "unconnected-(U20W-32.NC-Pad32)") (class "Default")
      (node (ref "U20W") (pin "32") (pinfunction "32.NC_32") (pintype "passive"))
    )
    (net (code "133") (name "unconnected-(U20W-33.IO21-Pad33)") (class "Default")
      (node (ref "U20W") (pin "33") (pinfunction "33.IO21_33") (pintype "passive"))
    )
    (net (code "134") (name "unconnected-(U20W-36.IO22-Pad36)") (class "Default")
      (node (ref "U20W") (pin "36") (pinfunction "36.IO22_36") (pintype "passive"))
    )
    (net (code "135") (name "unconnected-(U20W-37.IO23-Pad37)") (class "Default")
      (node (ref "U20W") (pin "37") (pinfunction "37.IO23_37") (pintype "passive"))
    )
    (net (code "136") (name "unconnected-(U30R-1.REF-Pad1)") (class "Default")
      (node (ref "U30R") (pin "1") (pinfunction "1.REF_1") (pintype "passive"))
    )
    (net (code "137") (name "~{OLED_RESET}") (class "Default")
      (node (ref "DIS20") (pin "7") (pinfunction "7.RST_7") (pintype "passive"))
      (node (ref "R20R") (pin "2") (pinfunction "2_2") (pintype "passive"))
    )
    (net (code "138") (name "~{RST}") (class "Default")
      (node (ref "C10R") (pin "1") (pinfunction "1_1") (pintype "passive"))
      (node (ref "RESET") (pin "1") (pinfunction "1-2_1") (pintype "passive"))
      (node (ref "U10") (pin "7") (pinfunction "7.~{RST}_7") (pintype "passive"))
    )
    (net (code "139") (name "~{SHT_PWR}") (class "Default")
      (node (ref "R30P") (pin "2") (pinfunction "2_2") (pintype "passive"))
      (node (ref "T30P") (pin "1") (pinfunction "G_1") (pintype "bidirectional"))
      (node (ref "U10") (pin "31") (pinfunction "31.PA10_31") (pintype "passive"))
    )
    (net (code "140") (name "~{SMBALERT}") (class "Default")
      (node (ref "R12P") (pin "1") (pinfunction "1_1") (pintype "passive"))
      (node (ref "U01C") (pin "12") (pinfunction "12.~{SMBALERT}_12") (pintype "passive"))
      (node (ref "U10") (pin "20") (pinfunction "20.PB2_20") (pintype "passive"))
    )
  )
)
